# Beta24_mt.net
KiCad netlist of a schematic drawn in EAGLE
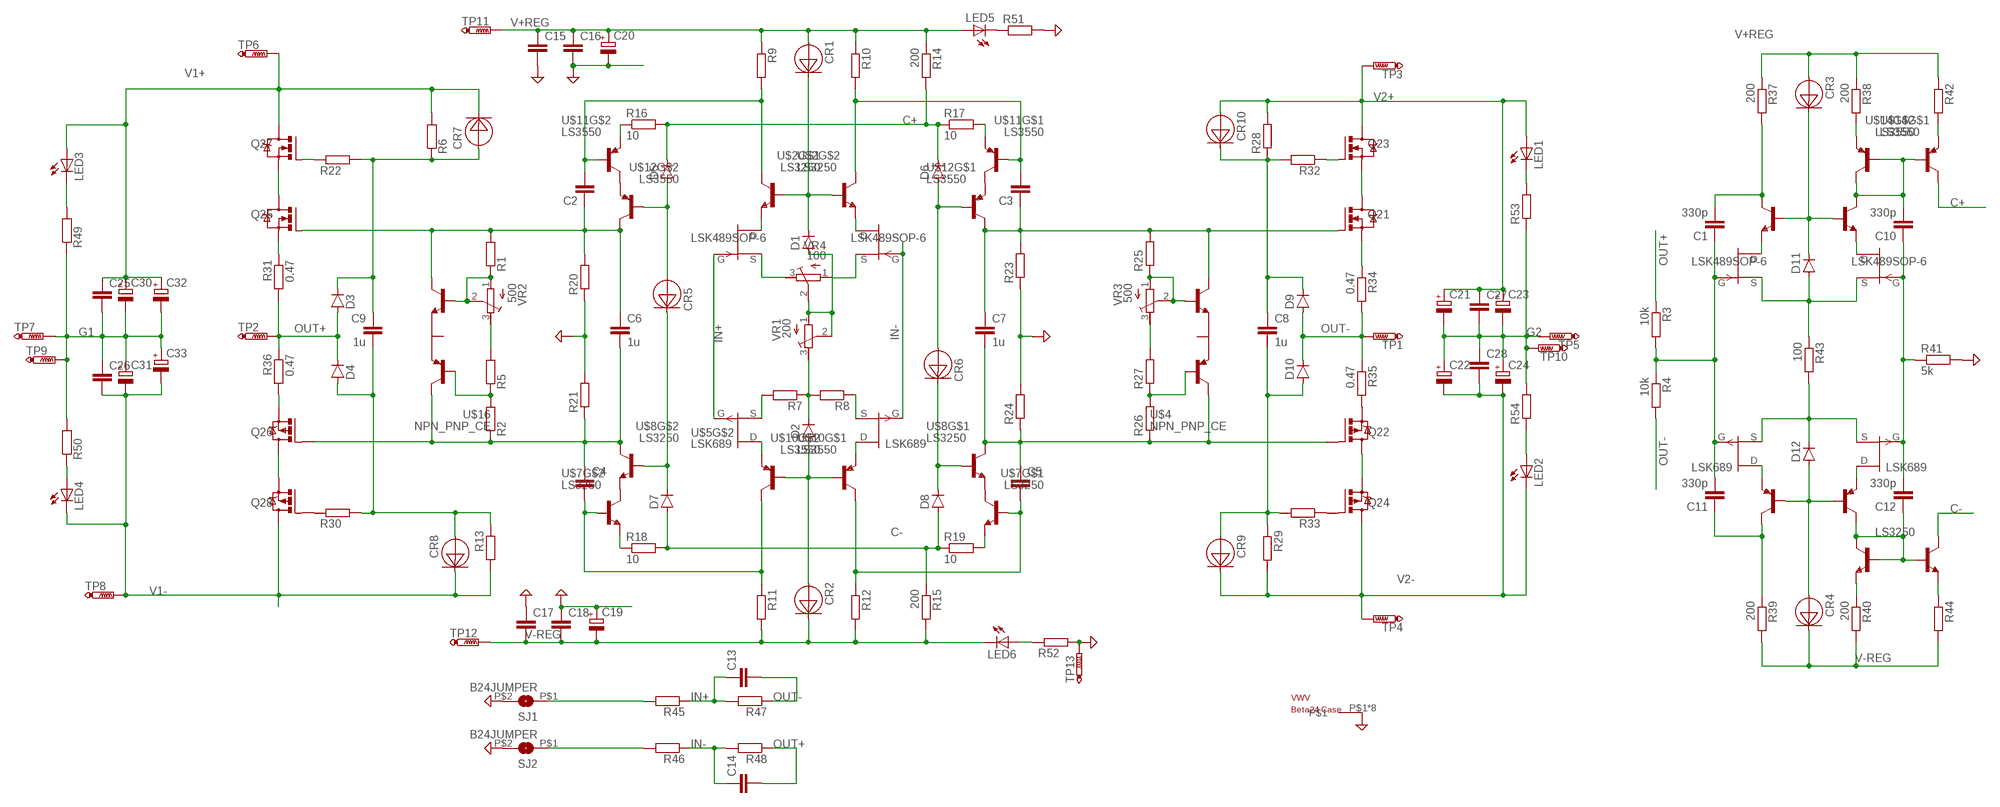
[diagram p0: schematic, sheet 1]

(export (version "E")
  (design (tool "Eeschema 10.0.6"))
  (components
    (comp (ref "C1")
      (value "330p")
      (footprint "eagle-import:C1206")
      (libsource (lib "eagle-import") (part "C-EUC1206"))
    )
    (comp (ref "C2")
      (value "C-EUC1206")
      (footprint "eagle-import:C1206")
      (libsource (lib "eagle-import") (part "C-EUC1206"))
    )
    (comp (ref "C3")
      (value "C-EUC1206")
      (footprint "eagle-import:C1206")
      (libsource (lib "eagle-import") (part "C-EUC1206"))
    )
    (comp (ref "C4")
      (value "C-EUC1206")
      (footprint "eagle-import:C1206")
      (libsource (lib "eagle-import") (part "C-EUC1206"))
    )
    (comp (ref "C5")
      (value "C-EUC1206")
      (footprint "eagle-import:C1206")
      (libsource (lib "eagle-import") (part "C-EUC1206"))
    )
    (comp (ref "C6")
      (value "1u")
      (footprint "eagle-import:C1210")
      (libsource (lib "eagle-import") (part "C-EUC1210"))
    )
    (comp (ref "C7")
      (value "1u")
      (footprint "eagle-import:C1210")
      (libsource (lib "eagle-import") (part "C-EUC1210"))
    )
    (comp (ref "C8")
      (value "1u")
      (footprint "eagle-import:C1206")
      (libsource (lib "eagle-import") (part "C-EUC1206"))
    )
    (comp (ref "C9")
      (value "1u")
      (footprint "eagle-import:C1206")
      (libsource (lib "eagle-import") (part "C-EUC1206"))
    )
    (comp (ref "C10")
      (value "330p")
      (footprint "eagle-import:C1206")
      (libsource (lib "eagle-import") (part "C-EUC1206"))
    )
    (comp (ref "C11")
      (value "330p")
      (footprint "eagle-import:C1206")
      (libsource (lib "eagle-import") (part "C-EUC1206"))
    )
    (comp (ref "C12")
      (value "330p")
      (footprint "eagle-import:C1206")
      (libsource (lib "eagle-import") (part "C-EUC1206"))
    )
    (comp (ref "C13")
      (value "C-EUC1206")
      (footprint "eagle-import:C1206")
      (libsource (lib "eagle-import") (part "C-EUC1206"))
    )
    (comp (ref "C14")
      (value "C-EUC1206")
      (footprint "eagle-import:C1206")
      (libsource (lib "eagle-import") (part "C-EUC1206"))
    )
    (comp (ref "C15")
      (value "C-EUC1206")
      (footprint "eagle-import:C1206")
      (libsource (lib "eagle-import") (part "C-EUC1206"))
    )
    (comp (ref "C16")
      (value "C-EUC1206")
      (footprint "eagle-import:C1206")
      (libsource (lib "eagle-import") (part "C-EUC1206"))
    )
    (comp (ref "C17")
      (value "C-EUC1206")
      (footprint "eagle-import:C1206")
      (libsource (lib "eagle-import") (part "C-EUC1206"))
    )
    (comp (ref "C18")
      (value "C-EUC1206")
      (footprint "eagle-import:C1206")
      (libsource (lib "eagle-import") (part "C-EUC1206"))
    )
    (comp (ref "C19")
      (value "CPOL-EUG")
      (footprint "eagle-import:PANASONIC_G")
      (libsource (lib "eagle-import") (part "CPOL-EUG"))
    )
    (comp (ref "C20")
      (value "CPOL-EUG")
      (footprint "eagle-import:PANASONIC_G")
      (libsource (lib "eagle-import") (part "CPOL-EUG"))
    )
    (comp (ref "C21")
      (value "CPOL-EUG")
      (footprint "eagle-import:PANASONIC_G")
      (libsource (lib "eagle-import") (part "CPOL-EUG"))
    )
    (comp (ref "C22")
      (value "CPOL-EUG")
      (footprint "eagle-import:PANASONIC_G")
      (libsource (lib "eagle-import") (part "CPOL-EUG"))
    )
    (comp (ref "C23")
      (value "CPOL-EUG")
      (footprint "eagle-import:PANASONIC_G")
      (libsource (lib "eagle-import") (part "CPOL-EUG"))
    )
    (comp (ref "C24")
      (value "CPOL-EUG")
      (footprint "eagle-import:PANASONIC_G")
      (libsource (lib "eagle-import") (part "CPOL-EUG"))
    )
    (comp (ref "C25")
      (value "C-EUC1206")
      (footprint "eagle-import:C1206")
      (libsource (lib "eagle-import") (part "C-EUC1206"))
    )
    (comp (ref "C26")
      (value "C-EUC1206")
      (footprint "eagle-import:C1206")
      (libsource (lib "eagle-import") (part "C-EUC1206"))
    )
    (comp (ref "C27")
      (value "C-EUC1206")
      (footprint "eagle-import:C1206")
      (libsource (lib "eagle-import") (part "C-EUC1206"))
    )
    (comp (ref "C28")
      (value "C-EUC1206")
      (footprint "eagle-import:C1206")
      (libsource (lib "eagle-import") (part "C-EUC1206"))
    )
    (comp (ref "C30")
      (value "CPOL-EUG")
      (footprint "eagle-import:PANASONIC_G")
      (libsource (lib "eagle-import") (part "CPOL-EUG"))
    )
    (comp (ref "C31")
      (value "CPOL-EUG")
      (footprint "eagle-import:PANASONIC_G")
      (libsource (lib "eagle-import") (part "CPOL-EUG"))
    )
    (comp (ref "C32")
      (value "CPOL-EUG")
      (footprint "eagle-import:PANASONIC_G")
      (libsource (lib "eagle-import") (part "CPOL-EUG"))
    )
    (comp (ref "C33")
      (value "CPOL-EUG")
      (footprint "eagle-import:PANASONIC_G")
      (libsource (lib "eagle-import") (part "CPOL-EUG"))
    )
    (comp (ref "CR1")
      (value "1N5283")
      (footprint "eagle-import:SMD")
      (libsource (lib "eagle-import") (part "1N5283"))
    )
    (comp (ref "CR2")
      (value "1N5283")
      (footprint "eagle-import:SMD")
      (libsource (lib "eagle-import") (part "1N5283"))
    )
    (comp (ref "CR3")
      (value "1N5283")
      (footprint "eagle-import:SMD")
      (libsource (lib "eagle-import") (part "1N5283"))
    )
    (comp (ref "CR4")
      (value "1N5283")
      (footprint "eagle-import:SMD")
      (libsource (lib "eagle-import") (part "1N5283"))
    )
    (comp (ref "CR5")
      (value "1N5283")
      (footprint "eagle-import:SMD")
      (libsource (lib "eagle-import") (part "1N5283"))
    )
    (comp (ref "CR6")
      (value "1N5283")
      (footprint "eagle-import:SMD")
      (libsource (lib "eagle-import") (part "1N5283"))
    )
    (comp (ref "CR7")
      (value "1N5283")
      (footprint "eagle-import:SMD")
      (libsource (lib "eagle-import") (part "1N5283"))
    )
    (comp (ref "CR8")
      (value "1N5283")
      (footprint "eagle-import:SMD")
      (libsource (lib "eagle-import") (part "1N5283"))
    )
    (comp (ref "CR9")
      (value "1N5283")
      (footprint "eagle-import:SMD")
      (libsource (lib "eagle-import") (part "1N5283"))
    )
    (comp (ref "CR10")
      (value "1N5283")
      (footprint "eagle-import:SMD")
      (libsource (lib "eagle-import") (part "1N5283"))
    )
    (comp (ref "D1")
      (value "DIODE-SOD80C")
      (footprint "eagle-import:SOD80C")
      (libsource (lib "eagle-import") (part "DIODE-SOD80C"))
    )
    (comp (ref "D2")
      (value "DIODE-SOD80C")
      (footprint "eagle-import:SOD80C")
      (libsource (lib "eagle-import") (part "DIODE-SOD80C"))
    )
    (comp (ref "D3")
      (value "DIODE-SOD80C")
      (footprint "eagle-import:SOD80C")
      (libsource (lib "eagle-import") (part "DIODE-SOD80C"))
    )
    (comp (ref "D4")
      (value "DIODE-SOD80C")
      (footprint "eagle-import:SOD80C")
      (libsource (lib "eagle-import") (part "DIODE-SOD80C"))
    )
    (comp (ref "D5")
      (value "DIODE-SOD80C")
      (footprint "eagle-import:SOD80C")
      (libsource (lib "eagle-import") (part "DIODE-SOD80C"))
    )
    (comp (ref "D6")
      (value "DIODE-SOD80C")
      (footprint "eagle-import:SOD80C")
      (libsource (lib "eagle-import") (part "DIODE-SOD80C"))
    )
    (comp (ref "D7")
      (value "DIODE-SOD80C")
      (footprint "eagle-import:SOD80C")
      (libsource (lib "eagle-import") (part "DIODE-SOD80C"))
    )
    (comp (ref "D8")
      (value "DIODE-SOD80C")
      (footprint "eagle-import:SOD80C")
      (libsource (lib "eagle-import") (part "DIODE-SOD80C"))
    )
    (comp (ref "D9")
      (value "DIODE-SOD80C")
      (footprint "eagle-import:SOD80C")
      (libsource (lib "eagle-import") (part "DIODE-SOD80C"))
    )
    (comp (ref "D10")
      (value "DIODE-SOD80C")
      (footprint "eagle-import:SOD80C")
      (libsource (lib "eagle-import") (part "DIODE-SOD80C"))
    )
    (comp (ref "D11")
      (value "DIODE-SOD80C")
      (footprint "eagle-import:SOD80C")
      (libsource (lib "eagle-import") (part "DIODE-SOD80C"))
    )
    (comp (ref "D12")
      (value "DIODE-SOD80C")
      (footprint "eagle-import:SOD80C")
      (libsource (lib "eagle-import") (part "DIODE-SOD80C"))
    )
    (comp (ref "LED1")
      (value "LED_LEDSML1206")
      (footprint "eagle-import:LED_SML1206")
      (libsource (lib "eagle-import") (part "LED_LEDSML1206"))
    )
    (comp (ref "LED2")
      (value "LED_LEDSML1206")
      (footprint "eagle-import:LED_SML1206")
      (libsource (lib "eagle-import") (part "LED_LEDSML1206"))
    )
    (comp (ref "LED3")
      (value "LED_LEDSML1206")
      (footprint "eagle-import:LED_SML1206")
      (libsource (lib "eagle-import") (part "LED_LEDSML1206"))
    )
    (comp (ref "LED4")
      (value "LED_LEDSML1206")
      (footprint "eagle-import:LED_SML1206")
      (libsource (lib "eagle-import") (part "LED_LEDSML1206"))
    )
    (comp (ref "LED5")
      (value "LED_LEDSML1206")
      (footprint "eagle-import:LED_SML1206")
      (libsource (lib "eagle-import") (part "LED_LEDSML1206"))
    )
    (comp (ref "LED6")
      (value "LED_LEDSML1206")
      (footprint "eagle-import:LED_SML1206")
      (libsource (lib "eagle-import") (part "LED_LEDSML1206"))
    )
    (comp (ref "Q21")
      (value "IRFZ24ND2PAK")
      (footprint "eagle-import:TO254P1054X240-3M")
      (libsource (lib "eagle-import") (part "IRFZ24ND2PAK"))
    )
    (comp (ref "Q22")
      (value "IRF9Z34D2PAK")
      (footprint "eagle-import:TO254P1054X240-3M")
      (libsource (lib "eagle-import") (part "IRF9Z34D2PAK"))
    )
    (comp (ref "Q23")
      (value "IRFZ24ND2PAK")
      (footprint "eagle-import:TO254P1054X240-3M")
      (libsource (lib "eagle-import") (part "IRFZ24ND2PAK"))
    )
    (comp (ref "Q24")
      (value "IRF9Z34D2PAK")
      (footprint "eagle-import:TO254P1054X240-3M")
      (libsource (lib "eagle-import") (part "IRF9Z34D2PAK"))
    )
    (comp (ref "Q25")
      (value "IRFZ24ND2PAK")
      (footprint "eagle-import:TO254P1054X240-3M")
      (libsource (lib "eagle-import") (part "IRFZ24ND2PAK"))
    )
    (comp (ref "Q26")
      (value "IRF9Z34D2PAK")
      (footprint "eagle-import:TO254P1054X240-3M")
      (libsource (lib "eagle-import") (part "IRF9Z34D2PAK"))
    )
    (comp (ref "Q27")
      (value "IRFZ24ND2PAK")
      (footprint "eagle-import:TO254P1054X240-3M")
      (libsource (lib "eagle-import") (part "IRFZ24ND2PAK"))
    )
    (comp (ref "Q28")
      (value "IRF9Z34D2PAK")
      (footprint "eagle-import:TO254P1054X240-3M")
      (libsource (lib "eagle-import") (part "IRF9Z34D2PAK"))
    )
    (comp (ref "R1")
      (value "R-EU_MELF0204W")
      (footprint "eagle-import:MINI_MELF-0204W")
      (libsource (lib "eagle-import") (part "R-EU_MELF0204W"))
    )
    (comp (ref "R2")
      (value "R-EU_MELF0204W")
      (footprint "eagle-import:MINI_MELF-0204W")
      (libsource (lib "eagle-import") (part "R-EU_MELF0204W"))
    )
    (comp (ref "R3")
      (value "10k")
      (footprint "eagle-import:MINI_MELF-0204W")
      (libsource (lib "eagle-import") (part "R-EU_MELF0204W"))
    )
    (comp (ref "R4")
      (value "10k")
      (footprint "eagle-import:MINI_MELF-0204W")
      (libsource (lib "eagle-import") (part "R-EU_MELF0204W"))
    )
    (comp (ref "R5")
      (value "R-EU_MELF0204W")
      (footprint "eagle-import:MINI_MELF-0204W")
      (libsource (lib "eagle-import") (part "R-EU_MELF0204W"))
    )
    (comp (ref "R6")
      (value "R-EU_MELF0204W")
      (footprint "eagle-import:MINI_MELF-0204W")
      (libsource (lib "eagle-import") (part "R-EU_MELF0204W"))
    )
    (comp (ref "R7")
      (value "R-EU_MELF0204W")
      (footprint "eagle-import:MINI_MELF-0204W")
      (libsource (lib "eagle-import") (part "R-EU_MELF0204W"))
    )
    (comp (ref "R8")
      (value "R-EU_MELF0204W")
      (footprint "eagle-import:MINI_MELF-0204W")
      (libsource (lib "eagle-import") (part "R-EU_MELF0204W"))
    )
    (comp (ref "R9")
      (value "R-EU_MELF0204W")
      (footprint "eagle-import:MINI_MELF-0204W")
      (libsource (lib "eagle-import") (part "R-EU_MELF0204W"))
    )
    (comp (ref "R10")
      (value "R-EU_MELF0204W")
      (footprint "eagle-import:MINI_MELF-0204W")
      (libsource (lib "eagle-import") (part "R-EU_MELF0204W"))
    )
    (comp (ref "R11")
      (value "R-EU_MELF0204W")
      (footprint "eagle-import:MINI_MELF-0204W")
      (libsource (lib "eagle-import") (part "R-EU_MELF0204W"))
    )
    (comp (ref "R12")
      (value "R-EU_MELF0204W")
      (footprint "eagle-import:MINI_MELF-0204W")
      (libsource (lib "eagle-import") (part "R-EU_MELF0204W"))
    )
    (comp (ref "R13")
      (value "R-EU_MELF0204W")
      (footprint "eagle-import:MINI_MELF-0204W")
      (libsource (lib "eagle-import") (part "R-EU_MELF0204W"))
    )
    (comp (ref "R14")
      (value "200")
      (footprint "eagle-import:MINI_MELF-0204W")
      (libsource (lib "eagle-import") (part "R-EU_MELF0204W"))
    )
    (comp (ref "R15")
      (value "200")
      (footprint "eagle-import:MINI_MELF-0204W")
      (libsource (lib "eagle-import") (part "R-EU_MELF0204W"))
    )
    (comp (ref "R16")
      (value "10")
      (footprint "eagle-import:MINI_MELF-0204W")
      (libsource (lib "eagle-import") (part "R-EU_MELF0204W"))
    )
    (comp (ref "R17")
      (value "10")
      (footprint "eagle-import:MINI_MELF-0204W")
      (libsource (lib "eagle-import") (part "R-EU_MELF0204W"))
    )
    (comp (ref "R18")
      (value "10")
      (footprint "eagle-import:MINI_MELF-0204W")
      (libsource (lib "eagle-import") (part "R-EU_MELF0204W"))
    )
    (comp (ref "R19")
      (value "10")
      (footprint "eagle-import:MINI_MELF-0204W")
      (libsource (lib "eagle-import") (part "R-EU_MELF0204W"))
    )
    (comp (ref "R20")
      (value "R-EU_MELF0204W")
      (footprint "eagle-import:MINI_MELF-0204W")
      (libsource (lib "eagle-import") (part "R-EU_MELF0204W"))
    )
    (comp (ref "R21")
      (value "R-EU_MELF0204W")
      (footprint "eagle-import:MINI_MELF-0204W")
      (libsource (lib "eagle-import") (part "R-EU_MELF0204W"))
    )
    (comp (ref "R22")
      (value "R-EU_MELF0204W")
      (footprint "eagle-import:MINI_MELF-0204W")
      (libsource (lib "eagle-import") (part "R-EU_MELF0204W"))
    )
    (comp (ref "R23")
      (value "R-EU_MELF0204W")
      (footprint "eagle-import:MINI_MELF-0204W")
      (libsource (lib "eagle-import") (part "R-EU_MELF0204W"))
    )
    (comp (ref "R24")
      (value "R-EU_MELF0204W")
      (footprint "eagle-import:MINI_MELF-0204W")
      (libsource (lib "eagle-import") (part "R-EU_MELF0204W"))
    )
    (comp (ref "R25")
      (value "R-EU_MELF0204W")
      (footprint "eagle-import:MINI_MELF-0204W")
      (libsource (lib "eagle-import") (part "R-EU_MELF0204W"))
    )
    (comp (ref "R26")
      (value "R-EU_MELF0204W")
      (footprint "eagle-import:MINI_MELF-0204W")
      (libsource (lib "eagle-import") (part "R-EU_MELF0204W"))
    )
    (comp (ref "R27")
      (value "R-EU_MELF0204W")
      (footprint "eagle-import:MINI_MELF-0204W")
      (libsource (lib "eagle-import") (part "R-EU_MELF0204W"))
    )
    (comp (ref "R28")
      (value "R-EU_MELF0204W")
      (footprint "eagle-import:MINI_MELF-0204W")
      (libsource (lib "eagle-import") (part "R-EU_MELF0204W"))
    )
    (comp (ref "R29")
      (value "R-EU_MELF0204W")
      (footprint "eagle-import:MINI_MELF-0204W")
      (libsource (lib "eagle-import") (part "R-EU_MELF0204W"))
    )
    (comp (ref "R30")
      (value "R-EU_MELF0204W")
      (footprint "eagle-import:MINI_MELF-0204W")
      (libsource (lib "eagle-import") (part "R-EU_MELF0204W"))
    )
    (comp (ref "R31")
      (value "0.47")
      (footprint "eagle-import:R2512")
      (libsource (lib "eagle-import") (part "R-EU_R2512"))
    )
    (comp (ref "R32")
      (value "R-EU_MELF0204W")
      (footprint "eagle-import:MINI_MELF-0204W")
      (libsource (lib "eagle-import") (part "R-EU_MELF0204W"))
    )
    (comp (ref "R33")
      (value "R-EU_MELF0204W")
      (footprint "eagle-import:MINI_MELF-0204W")
      (libsource (lib "eagle-import") (part "R-EU_MELF0204W"))
    )
    (comp (ref "R34")
      (value "0.47")
      (footprint "eagle-import:R2512")
      (libsource (lib "eagle-import") (part "R-EU_R2512"))
    )
    (comp (ref "R35")
      (value "0.47")
      (footprint "eagle-import:R2512")
      (libsource (lib "eagle-import") (part "R-EU_R2512"))
    )
    (comp (ref "R36")
      (value "0.47")
      (footprint "eagle-import:R2512")
      (libsource (lib "eagle-import") (part "R-EU_R2512"))
    )
    (comp (ref "R37")
      (value "200")
      (footprint "eagle-import:MINI_MELF-0204W")
      (libsource (lib "eagle-import") (part "R-EU_MELF0204W"))
    )
    (comp (ref "R38")
      (value "200")
      (footprint "eagle-import:MINI_MELF-0204W")
      (libsource (lib "eagle-import") (part "R-EU_MELF0204W"))
    )
    (comp (ref "R39")
      (value "200")
      (footprint "eagle-import:MINI_MELF-0204W")
      (libsource (lib "eagle-import") (part "R-EU_MELF0204W"))
    )
    (comp (ref "R40")
      (value "200")
      (footprint "eagle-import:MINI_MELF-0204W")
      (libsource (lib "eagle-import") (part "R-EU_MELF0204W"))
    )
    (comp (ref "R41")
      (value "5k")
      (footprint "eagle-import:MINI_MELF-0204W")
      (libsource (lib "eagle-import") (part "R-EU_MELF0204W"))
    )
    (comp (ref "R42")
      (value "R-EU_MELF0204W")
      (footprint "eagle-import:MINI_MELF-0204W")
      (libsource (lib "eagle-import") (part "R-EU_MELF0204W"))
    )
    (comp (ref "R43")
      (value "100")
      (footprint "eagle-import:MINI_MELF-0204W")
      (libsource (lib "eagle-import") (part "R-EU_MELF0204W"))
    )
    (comp (ref "R44")
      (value "R-EU_MELF0204W")
      (footprint "eagle-import:MINI_MELF-0204W")
      (libsource (lib "eagle-import") (part "R-EU_MELF0204W"))
    )
    (comp (ref "R45")
      (value "R-EU_MELF0204W")
      (footprint "eagle-import:MINI_MELF-0204W")
      (libsource (lib "eagle-import") (part "R-EU_MELF0204W"))
    )
    (comp (ref "R46")
      (value "R-EU_MELF0204W")
      (footprint "eagle-import:MINI_MELF-0204W")
      (libsource (lib "eagle-import") (part "R-EU_MELF0204W"))
    )
    (comp (ref "R47")
      (value "R-EU_MELF0204W")
      (footprint "eagle-import:MINI_MELF-0204W")
      (libsource (lib "eagle-import") (part "R-EU_MELF0204W"))
    )
    (comp (ref "R48")
      (value "R-EU_MELF0204W")
      (footprint "eagle-import:MINI_MELF-0204W")
      (libsource (lib "eagle-import") (part "R-EU_MELF0204W"))
    )
    (comp (ref "R49")
      (value "R-EU_MELF0204W")
      (footprint "eagle-import:MINI_MELF-0204W")
      (libsource (lib "eagle-import") (part "R-EU_MELF0204W"))
    )
    (comp (ref "R50")
      (value "R-EU_MELF0204W")
      (footprint "eagle-import:MINI_MELF-0204W")
      (libsource (lib "eagle-import") (part "R-EU_MELF0204W"))
    )
    (comp (ref "R51")
      (value "200")
      (footprint "eagle-import:MINI_MELF-0204W")
      (libsource (lib "eagle-import") (part "R-EU_MELF0204W"))
    )
    (comp (ref "R52")
      (value "R-EU_MELF0204W")
      (footprint "eagle-import:MINI_MELF-0204W")
      (libsource (lib "eagle-import") (part "R-EU_MELF0204W"))
    )
    (comp (ref "R53")
      (value "R-EU_MELF0204W")
      (footprint "eagle-import:MINI_MELF-0204W")
      (libsource (lib "eagle-import") (part "R-EU_MELF0204W"))
    )
    (comp (ref "R54")
      (value "R-EU_MELF0204W")
      (footprint "eagle-import:MINI_MELF-0204W")
      (libsource (lib "eagle-import") (part "R-EU_MELF0204W"))
    )
    (comp (ref "SJ1")
      (value "B24JUMPER")
      (footprint "eagle-import:B24J")
      (libsource (lib "eagle-import") (part "B24JUMPER"))
    )
    (comp (ref "SJ2")
      (value "B24JUMPER")
      (footprint "eagle-import:B24J")
      (libsource (lib "eagle-import") (part "B24JUMPER"))
    )
    (comp (ref "TP1")
      (value "PTR1PAD1-20")
      (footprint "eagle-import:P1-20")
      (libsource (lib "eagle-import") (part "PTR1PAD1-20"))
    )
    (comp (ref "TP2")
      (value "PTR1PAD1-20")
      (footprint "eagle-import:P1-20")
      (libsource (lib "eagle-import") (part "PTR1PAD1-20"))
    )
    (comp (ref "TP3")
      (value "PTR1PAD1-20")
      (footprint "eagle-import:P1-20")
      (libsource (lib "eagle-import") (part "PTR1PAD1-20"))
    )
    (comp (ref "TP4")
      (value "PTR1PAD1-20")
      (footprint "eagle-import:P1-20")
      (libsource (lib "eagle-import") (part "PTR1PAD1-20"))
    )
    (comp (ref "TP5")
      (value "PTR1PAD1-20")
      (footprint "eagle-import:P1-20")
      (libsource (lib "eagle-import") (part "PTR1PAD1-20"))
    )
    (comp (ref "TP6")
      (value "PTR1PAD1-20")
      (footprint "eagle-import:P1-20")
      (libsource (lib "eagle-import") (part "PTR1PAD1-20"))
    )
    (comp (ref "TP7")
      (value "PTR1PAD1-20")
      (footprint "eagle-import:P1-20")
      (libsource (lib "eagle-import") (part "PTR1PAD1-20"))
    )
    (comp (ref "TP8")
      (value "PTR1PAD1-20")
      (footprint "eagle-import:P1-20")
      (libsource (lib "eagle-import") (part "PTR1PAD1-20"))
    )
    (comp (ref "TP9")
      (value "PTR1PAD1-20")
      (footprint "eagle-import:P1-20")
      (libsource (lib "eagle-import") (part "PTR1PAD1-20"))
    )
    (comp (ref "TP10")
      (value "PTR1PAD1-20")
      (footprint "eagle-import:P1-20")
      (libsource (lib "eagle-import") (part "PTR1PAD1-20"))
    )
    (comp (ref "TP11")
      (value "PTR1PAD1-20")
      (footprint "eagle-import:P1-20")
      (libsource (lib "eagle-import") (part "PTR1PAD1-20"))
    )
    (comp (ref "TP12")
      (value "PTR1PAD1-20")
      (footprint "eagle-import:P1-20")
      (libsource (lib "eagle-import") (part "PTR1PAD1-20"))
    )
    (comp (ref "TP13")
      (value "PTR1PAD1-20")
      (footprint "eagle-import:P1-20")
      (libsource (lib "eagle-import") (part "PTR1PAD1-20"))
    )
    (comp (ref "U$1")
      (value "LSK489SOP-6")
      (footprint "eagle-import:SOT-23-6")
      (libsource (lib "eagle-import") (part "LSK489SOP-6"))
    )
    (comp (ref "U$2")
      (value "LS3250")
      (footprint "eagle-import:SOT-23-6")
      (libsource (lib "eagle-import") (part "LS3250"))
    )
    (comp (ref "U$3")
      (value "LSK489SOP-6")
      (footprint "eagle-import:SOT-23-6")
      (libsource (lib "eagle-import") (part "LSK489SOP-6"))
    )
    (comp (ref "U$4")
      (value "NPN_PNP_CE")
      (footprint "eagle-import:SOT25")
      (libsource (lib "eagle-import") (part "NPN_PNP_CE"))
    )
    (comp (ref "U$5")
      (value "LSK689")
      (footprint "eagle-import:SOT-23-6")
      (libsource (lib "eagle-import") (part "LSK689"))
    )
    (comp (ref "U$6")
      (value "LS3250")
      (footprint "eagle-import:SOT-23-6")
      (libsource (lib "eagle-import") (part "LS3250"))
    )
    (comp (ref "U$7")
      (value "LS3250")
      (footprint "eagle-import:SOT-23-6")
      (libsource (lib "eagle-import") (part "LS3250"))
    )
    (comp (ref "U$8")
      (value "LS3250")
      (footprint "eagle-import:SOT-23-6")
      (libsource (lib "eagle-import") (part "LS3250"))
    )
    (comp (ref "U$9")
      (value "LS3550")
      (footprint "eagle-import:SOT-23-6")
      (libsource (lib "eagle-import") (part "LS3550"))
    )
    (comp (ref "U$10")
      (value "LS3550")
      (footprint "eagle-import:SOT-23-6")
      (libsource (lib "eagle-import") (part "LS3550"))
    )
    (comp (ref "U$11")
      (value "LS3550")
      (footprint "eagle-import:SOT-23-6")
      (libsource (lib "eagle-import") (part "LS3550"))
    )
    (comp (ref "U$12")
      (value "LS3550")
      (footprint "eagle-import:SOT-23-6")
      (libsource (lib "eagle-import") (part "LS3550"))
    )
    (comp (ref "U$13")
      (value "LS3250")
      (footprint "eagle-import:SOT-23-6")
      (libsource (lib "eagle-import") (part "LS3250"))
    )
    (comp (ref "U$14")
      (value "LS3550")
      (footprint "eagle-import:SOT-23-6")
      (libsource (lib "eagle-import") (part "LS3550"))
    )
    (comp (ref "U$15")
      (value "LSK689")
      (footprint "eagle-import:SOT-23-6")
      (libsource (lib "eagle-import") (part "LSK689"))
    )
    (comp (ref "U$16")
      (value "NPN_PNP_CE")
      (footprint "eagle-import:SOT25")
      (libsource (lib "eagle-import") (part "NPN_PNP_CE"))
    )
    (comp (ref "U$17")
      (value "VWV")
      (footprint "eagle-import:VWV")
      (libsource (lib "eagle-import") (part "VWV"))
    )
    (comp (ref "U$18")
      (value "B24C")
      (footprint "eagle-import:B24C")
      (libsource (lib "eagle-import") (part "B24C"))
    )
    (comp (ref "VR1")
      (value "200")
      (footprint "eagle-import:RTRIM3296W")
      (libsource (lib "eagle-import") (part "R-TRIMM3296W"))
    )
    (comp (ref "VR2")
      (value "500")
      (footprint "eagle-import:RTRIM3296W")
      (libsource (lib "eagle-import") (part "R-TRIMM3296W"))
    )
    (comp (ref "VR3")
      (value "500")
      (footprint "eagle-import:RTRIM3296W")
      (libsource (lib "eagle-import") (part "R-TRIMM3296W"))
    )
    (comp (ref "VR4")
      (value "100")
      (footprint "eagle-import:RTRIM3296W")
      (libsource (lib "eagle-import") (part "R-TRIMM3296W"))
    )
  )
  (nets
    (net (code "1") (name "/C+") (class "Default")
      (node (ref "D5") (pin "C") (pinfunction "C_C") (pintype "passive"))
      (node (ref "D6") (pin "C") (pinfunction "C_C") (pintype "passive"))
      (node (ref "R14") (pin "2") (pinfunction "2_2") (pintype "passive"))
      (node (ref "R16") (pin "2") (pinfunction "2_2") (pintype "passive"))
      (node (ref "R17") (pin "1") (pinfunction "1_1") (pintype "passive"))
      (node (ref "U$14") (pin "6") (pinfunction "C_6") (pintype "passive"))
    )
    (net (code "2") (name "/C-") (class "Default")
      (node (ref "D7") (pin "A") (pinfunction "A_A") (pintype "passive"))
      (node (ref "D8") (pin "A") (pinfunction "A_A") (pintype "passive"))
      (node (ref "R15") (pin "1") (pinfunction "1_1") (pintype "passive"))
      (node (ref "R18") (pin "2") (pinfunction "2_2") (pintype "passive"))
      (node (ref "R19") (pin "1") (pinfunction "1_1") (pintype "passive"))
      (node (ref "U$13") (pin "6") (pinfunction "C_6") (pintype "passive"))
    )
    (net (code "3") (name "/G1") (class "Default")
      (node (ref "C25") (pin "2") (pinfunction "2_2") (pintype "passive"))
      (node (ref "C26") (pin "1") (pinfunction "1_1") (pintype "passive"))
      (node (ref "C30") (pin "-") (pinfunction "-_-") (pintype "passive"))
      (node (ref "C31") (pin "+") (pinfunction "+_+") (pintype "passive"))
      (node (ref "C32") (pin "-") (pinfunction "-_-") (pintype "passive"))
      (node (ref "C33") (pin "+") (pinfunction "+_+") (pintype "passive"))
      (node (ref "R49") (pin "1") (pinfunction "1_1") (pintype "passive"))
      (node (ref "R50") (pin "2") (pinfunction "2_2") (pintype "passive"))
      (node (ref "TP7") (pin "TP") (pinfunction "TP_TP") (pintype "input"))
      (node (ref "TP9") (pin "TP") (pinfunction "TP_TP") (pintype "input"))
    )
    (net (code "4") (name "/G2") (class "Default")
      (node (ref "C21") (pin "-") (pinfunction "-_-") (pintype "passive"))
      (node (ref "C22") (pin "+") (pinfunction "+_+") (pintype "passive"))
      (node (ref "C23") (pin "-") (pinfunction "-_-") (pintype "passive"))
      (node (ref "C24") (pin "+") (pinfunction "+_+") (pintype "passive"))
      (node (ref "C27") (pin "2") (pinfunction "2_2") (pintype "passive"))
      (node (ref "C28") (pin "1") (pinfunction "1_1") (pintype "passive"))
      (node (ref "R53") (pin "1") (pinfunction "1_1") (pintype "passive"))
      (node (ref "R54") (pin "2") (pinfunction "2_2") (pintype "passive"))
      (node (ref "TP10") (pin "TP") (pinfunction "TP_TP") (pintype "input"))
      (node (ref "TP5") (pin "TP") (pinfunction "TP_TP") (pintype "input"))
    )
    (net (code "5") (name "/IN+") (class "Default")
      (node (ref "C13") (pin "1") (pinfunction "1_1") (pintype "passive"))
      (node (ref "R45") (pin "1") (pinfunction "1_1") (pintype "passive"))
      (node (ref "R47") (pin "2") (pinfunction "2_2") (pintype "passive"))
      (node (ref "U$1") (pin "1") (pinfunction "G_1") (pintype "passive"))
      (node (ref "U$5") (pin "4") (pinfunction "G_4") (pintype "passive"))
    )
    (net (code "6") (name "/IN-") (class "Default")
      (node (ref "C14") (pin "1") (pinfunction "1_1") (pintype "passive"))
      (node (ref "R46") (pin "1") (pinfunction "1_1") (pintype "passive"))
      (node (ref "R48") (pin "2") (pinfunction "2_2") (pintype "passive"))
      (node (ref "U$1") (pin "4") (pinfunction "G_4") (pintype "passive"))
      (node (ref "U$5") (pin "1") (pinfunction "G_1") (pintype "passive"))
    )
    (net (code "7") (name "/OUT+") (class "Default")
      (node (ref "C14") (pin "2") (pinfunction "2_2") (pintype "passive"))
      (node (ref "D3") (pin "A") (pinfunction "A_A") (pintype "passive"))
      (node (ref "D4") (pin "C") (pinfunction "C_C") (pintype "passive"))
      (node (ref "R3") (pin "1") (pinfunction "1_1") (pintype "passive"))
      (node (ref "R31") (pin "2") (pinfunction "2_2") (pintype "passive"))
      (node (ref "R36") (pin "1") (pinfunction "1_1") (pintype "passive"))
      (node (ref "R48") (pin "1") (pinfunction "1_1") (pintype "passive"))
      (node (ref "TP2") (pin "TP") (pinfunction "TP_TP") (pintype "input"))
    )
    (net (code "8") (name "/OUT-") (class "Default")
      (node (ref "C13") (pin "2") (pinfunction "2_2") (pintype "passive"))
      (node (ref "D10") (pin "C") (pinfunction "C_C") (pintype "passive"))
      (node (ref "D9") (pin "A") (pinfunction "A_A") (pintype "passive"))
      (node (ref "R34") (pin "2") (pinfunction "2_2") (pintype "passive"))
      (node (ref "R35") (pin "1") (pinfunction "1_1") (pintype "passive"))
      (node (ref "R4") (pin "2") (pinfunction "2_2") (pintype "passive"))
      (node (ref "R47") (pin "1") (pinfunction "1_1") (pintype "passive"))
      (node (ref "TP1") (pin "TP") (pinfunction "TP_TP") (pintype "input"))
    )
    (net (code "9") (name "/V+REG") (class "Default")
      (node (ref "C15") (pin "1") (pinfunction "1_1") (pintype "passive"))
      (node (ref "C16") (pin "1") (pinfunction "1_1") (pintype "passive"))
      (node (ref "C20") (pin "+") (pinfunction "+_+") (pintype "passive"))
      (node (ref "CR1") (pin "ANODE") (pinfunction "ANODE_ANODE") (pintype "passive"))
      (node (ref "CR3") (pin "ANODE") (pinfunction "ANODE_ANODE") (pintype "passive"))
      (node (ref "LED5") (pin "A") (pinfunction "A_A") (pintype "passive"))
      (node (ref "R10") (pin "1") (pinfunction "1_1") (pintype "passive"))
      (node (ref "R14") (pin "1") (pinfunction "1_1") (pintype "passive"))
      (node (ref "R37") (pin "1") (pinfunction "1_1") (pintype "passive"))
      (node (ref "R38") (pin "1") (pinfunction "1_1") (pintype "passive"))
      (node (ref "R42") (pin "1") (pinfunction "1_1") (pintype "passive"))
      (node (ref "R9") (pin "1") (pinfunction "1_1") (pintype "passive"))
      (node (ref "TP11") (pin "TP") (pinfunction "TP_TP") (pintype "input"))
    )
    (net (code "10") (name "/V-REG") (class "Default")
      (node (ref "C17") (pin "2") (pinfunction "2_2") (pintype "passive"))
      (node (ref "C18") (pin "2") (pinfunction "2_2") (pintype "passive"))
      (node (ref "C19") (pin "-") (pinfunction "-_-") (pintype "passive"))
      (node (ref "CR2") (pin "CATHODE") (pinfunction "CATHODE_CATHODE") (pintype "passive"))
      (node (ref "CR4") (pin "CATHODE") (pinfunction "CATHODE_CATHODE") (pintype "passive"))
      (node (ref "LED6") (pin "C") (pinfunction "C_C") (pintype "passive"))
      (node (ref "R11") (pin "2") (pinfunction "2_2") (pintype "passive"))
      (node (ref "R12") (pin "2") (pinfunction "2_2") (pintype "passive"))
      (node (ref "R15") (pin "2") (pinfunction "2_2") (pintype "passive"))
      (node (ref "R39") (pin "2") (pinfunction "2_2") (pintype "passive"))
      (node (ref "R40") (pin "2") (pinfunction "2_2") (pintype "passive"))
      (node (ref "R44") (pin "2") (pinfunction "2_2") (pintype "passive"))
      (node (ref "TP12") (pin "TP") (pinfunction "TP_TP") (pintype "input"))
    )
    (net (code "11") (name "/V1+") (class "Default")
      (node (ref "C25") (pin "1") (pinfunction "1_1") (pintype "passive"))
      (node (ref "C30") (pin "+") (pinfunction "+_+") (pintype "passive"))
      (node (ref "C32") (pin "+") (pinfunction "+_+") (pintype "passive"))
      (node (ref "CR7") (pin "CATHODE") (pinfunction "CATHODE_CATHODE") (pintype "passive"))
      (node (ref "LED3") (pin "A") (pinfunction "A_A") (pintype "passive"))
      (node (ref "Q27") (pin "2") (pinfunction "D_2") (pintype "passive"))
      (node (ref "Q27") (pin "4") (pinfunction "D_4") (pintype "passive"))
      (node (ref "Q27") (pin "P$1") (pinfunction "D_P$1") (pintype "passive"))
      (node (ref "Q27") (pin "P$10") (pinfunction "D_P$10") (pintype "passive"))
      (node (ref "Q27") (pin "P$11") (pinfunction "D_P$11") (pintype "passive"))
      (node (ref "Q27") (pin "P$12") (pinfunction "D_P$12") (pintype "passive"))
      (node (ref "Q27") (pin "P$13") (pinfunction "D_P$13") (pintype "passive"))
      (node (ref "Q27") (pin "P$14") (pinfunction "D_P$14") (pintype "passive"))
      (node (ref "Q27") (pin "P$15") (pinfunction "D_P$15") (pintype "passive"))
      (node (ref "Q27") (pin "P$16") (pinfunction "D_P$16") (pintype "passive"))
      (node (ref "Q27") (pin "P$17") (pinfunction "D_P$17") (pintype "passive"))
      (node (ref "Q27") (pin "P$18") (pinfunction "D_P$18") (pintype "passive"))
      (node (ref "Q27") (pin "P$19") (pinfunction "D_P$19") (pintype "passive"))
      (node (ref "Q27") (pin "P$2") (pinfunction "D_P$2") (pintype "passive"))
      (node (ref "Q27") (pin "P$20") (pinfunction "D_P$20") (pintype "passive"))
      (node (ref "Q27") (pin "P$21") (pinfunction "D_P$21") (pintype "passive"))
      (node (ref "Q27") (pin "P$22") (pinfunction "D_P$22") (pintype "passive"))
      (node (ref "Q27") (pin "P$23") (pinfunction "D_P$23") (pintype "passive"))
      (node (ref "Q27") (pin "P$24") (pinfunction "D_P$24") (pintype "passive"))
      (node (ref "Q27") (pin "P$25") (pinfunction "D_P$25") (pintype "passive"))
      (node (ref "Q27") (pin "P$26") (pinfunction "D_P$26") (pintype "passive"))
      (node (ref "Q27") (pin "P$27") (pinfunction "D_P$27") (pintype "passive"))
      (node (ref "Q27") (pin "P$28") (pinfunction "D_P$28") (pintype "passive"))
      (node (ref "Q27") (pin "P$29") (pinfunction "D_P$29") (pintype "passive"))
      (node (ref "Q27") (pin "P$3") (pinfunction "D_P$3") (pintype "passive"))
      (node (ref "Q27") (pin "P$30") (pinfunction "D_P$30") (pintype "passive"))
      (node (ref "Q27") (pin "P$31") (pinfunction "D_P$31") (pintype "passive"))
      (node (ref "Q27") (pin "P$32") (pinfunction "D_P$32") (pintype "passive"))
      (node (ref "Q27") (pin "P$33") (pinfunction "D_P$33") (pintype "passive"))
      (node (ref "Q27") (pin "P$34") (pinfunction "D_P$34") (pintype "passive"))
      (node (ref "Q27") (pin "P$35") (pinfunction "D_P$35") (pintype "passive"))
      (node (ref "Q27") (pin "P$36") (pinfunction "D_P$36") (pintype "passive"))
      (node (ref "Q27") (pin "P$37") (pinfunction "D_P$37") (pintype "passive"))
      (node (ref "Q27") (pin "P$38") (pinfunction "D_P$38") (pintype "passive"))
      (node (ref "Q27") (pin "P$39") (pinfunction "D_P$39") (pintype "passive"))
      (node (ref "Q27") (pin "P$4") (pinfunction "D_P$4") (pintype "passive"))
      (node (ref "Q27") (pin "P$40") (pinfunction "D_P$40") (pintype "passive"))
      (node (ref "Q27") (pin "P$41") (pinfunction "D_P$41") (pintype "passive"))
      (node (ref "Q27") (pin "P$42") (pinfunction "D_P$42") (pintype "passive"))
      (node (ref "Q27") (pin "P$43") (pinfunction "D_P$43") (pintype "passive"))
      (node (ref "Q27") (pin "P$44") (pinfunction "D_P$44") (pintype "passive"))
      (node (ref "Q27") (pin "P$45") (pinfunction "D_P$45") (pintype "passive"))
      (node (ref "Q27") (pin "P$46") (pinfunction "D_P$46") (pintype "passive"))
      (node (ref "Q27") (pin "P$47") (pinfunction "D_P$47") (pintype "passive"))
      (node (ref "Q27") (pin "P$48") (pinfunction "D_P$48") (pintype "passive"))
      (node (ref "Q27") (pin "P$49") (pinfunction "D_P$49") (pintype "passive"))
      (node (ref "Q27") (pin "P$5") (pinfunction "D_P$5") (pintype "passive"))
      (node (ref "Q27") (pin "P$50") (pinfunction "D_P$50") (pintype "passive"))
      (node (ref "Q27") (pin "P$51") (pinfunction "D_P$51") (pintype "passive"))
      (node (ref "Q27") (pin "P$52") (pinfunction "D_P$52") (pintype "passive"))
      (node (ref "Q27") (pin "P$53") (pinfunction "D_P$53") (pintype "passive"))
      (node (ref "Q27") (pin "P$54") (pinfunction "D_P$54") (pintype "passive"))
      (node (ref "Q27") (pin "P$55") (pinfunction "D_P$55") (pintype "passive"))
      (node (ref "Q27") (pin "P$56") (pinfunction "D_P$56") (pintype "passive"))
      (node (ref "Q27") (pin "P$57") (pinfunction "D_P$57") (pintype "passive"))
      (node (ref "Q27") (pin "P$58") (pinfunction "D_P$58") (pintype "passive"))
      (node (ref "Q27") (pin "P$59") (pinfunction "D_P$59") (pintype "passive"))
      (node (ref "Q27") (pin "P$6") (pinfunction "D_P$6") (pintype "passive"))
      (node (ref "Q27") (pin "P$60") (pinfunction "D_P$60") (pintype "passive"))
      (node (ref "Q27") (pin "P$61") (pinfunction "D_P$61") (pintype "passive"))
      (node (ref "Q27") (pin "P$62") (pinfunction "D_P$62") (pintype "passive"))
      (node (ref "Q27") (pin "P$63") (pinfunction "D_P$63") (pintype "passive"))
      (node (ref "Q27") (pin "P$7") (pinfunction "D_P$7") (pintype "passive"))
      (node (ref "Q27") (pin "P$8") (pinfunction "D_P$8") (pintype "passive"))
      (node (ref "Q27") (pin "P$9") (pinfunction "D_P$9") (pintype "passive"))
      (node (ref "R6") (pin "2") (pinfunction "2_2") (pintype "passive"))
      (node (ref "TP6") (pin "TP") (pinfunction "TP_TP") (pintype "input"))
    )
    (net (code "12") (name "/V1-") (class "Default")
      (node (ref "C26") (pin "2") (pinfunction "2_2") (pintype "passive"))
      (node (ref "C31") (pin "-") (pinfunction "-_-") (pintype "passive"))
      (node (ref "C33") (pin "-") (pinfunction "-_-") (pintype "passive"))
      (node (ref "CR8") (pin "CATHODE") (pinfunction "CATHODE_CATHODE") (pintype "passive"))
      (node (ref "LED4") (pin "C") (pinfunction "C_C") (pintype "passive"))
      (node (ref "Q28") (pin "2") (pinfunction "D_2") (pintype "passive"))
      (node (ref "Q28") (pin "4") (pinfunction "D_4") (pintype "passive"))
      (node (ref "Q28") (pin "P$1") (pinfunction "D_P$1") (pintype "passive"))
      (node (ref "Q28") (pin "P$10") (pinfunction "D_P$10") (pintype "passive"))
      (node (ref "Q28") (pin "P$11") (pinfunction "D_P$11") (pintype "passive"))
      (node (ref "Q28") (pin "P$12") (pinfunction "D_P$12") (pintype "passive"))
      (node (ref "Q28") (pin "P$13") (pinfunction "D_P$13") (pintype "passive"))
      (node (ref "Q28") (pin "P$14") (pinfunction "D_P$14") (pintype "passive"))
      (node (ref "Q28") (pin "P$15") (pinfunction "D_P$15") (pintype "passive"))
      (node (ref "Q28") (pin "P$16") (pinfunction "D_P$16") (pintype "passive"))
      (node (ref "Q28") (pin "P$17") (pinfunction "D_P$17") (pintype "passive"))
      (node (ref "Q28") (pin "P$18") (pinfunction "D_P$18") (pintype "passive"))
      (node (ref "Q28") (pin "P$19") (pinfunction "D_P$19") (pintype "passive"))
      (node (ref "Q28") (pin "P$2") (pinfunction "D_P$2") (pintype "passive"))
      (node (ref "Q28") (pin "P$20") (pinfunction "D_P$20") (pintype "passive"))
      (node (ref "Q28") (pin "P$21") (pinfunction "D_P$21") (pintype "passive"))
      (node (ref "Q28") (pin "P$22") (pinfunction "D_P$22") (pintype "passive"))
      (node (ref "Q28") (pin "P$23") (pinfunction "D_P$23") (pintype "passive"))
      (node (ref "Q28") (pin "P$24") (pinfunction "D_P$24") (pintype "passive"))
      (node (ref "Q28") (pin "P$25") (pinfunction "D_P$25") (pintype "passive"))
      (node (ref "Q28") (pin "P$26") (pinfunction "D_P$26") (pintype "passive"))
      (node (ref "Q28") (pin "P$27") (pinfunction "D_P$27") (pintype "passive"))
      (node (ref "Q28") (pin "P$28") (pinfunction "D_P$28") (pintype "passive"))
      (node (ref "Q28") (pin "P$29") (pinfunction "D_P$29") (pintype "passive"))
      (node (ref "Q28") (pin "P$3") (pinfunction "D_P$3") (pintype "passive"))
      (node (ref "Q28") (pin "P$30") (pinfunction "D_P$30") (pintype "passive"))
      (node (ref "Q28") (pin "P$31") (pinfunction "D_P$31") (pintype "passive"))
      (node (ref "Q28") (pin "P$32") (pinfunction "D_P$32") (pintype "passive"))
      (node (ref "Q28") (pin "P$33") (pinfunction "D_P$33") (pintype "passive"))
      (node (ref "Q28") (pin "P$34") (pinfunction "D_P$34") (pintype "passive"))
      (node (ref "Q28") (pin "P$35") (pinfunction "D_P$35") (pintype "passive"))
      (node (ref "Q28") (pin "P$36") (pinfunction "D_P$36") (pintype "passive"))
      (node (ref "Q28") (pin "P$37") (pinfunction "D_P$37") (pintype "passive"))
      (node (ref "Q28") (pin "P$38") (pinfunction "D_P$38") (pintype "passive"))
      (node (ref "Q28") (pin "P$39") (pinfunction "D_P$39") (pintype "passive"))
      (node (ref "Q28") (pin "P$4") (pinfunction "D_P$4") (pintype "passive"))
      (node (ref "Q28") (pin "P$40") (pinfunction "D_P$40") (pintype "passive"))
      (node (ref "Q28") (pin "P$41") (pinfunction "D_P$41") (pintype "passive"))
      (node (ref "Q28") (pin "P$42") (pinfunction "D_P$42") (pintype "passive"))
      (node (ref "Q28") (pin "P$43") (pinfunction "D_P$43") (pintype "passive"))
      (node (ref "Q28") (pin "P$44") (pinfunction "D_P$44") (pintype "passive"))
      (node (ref "Q28") (pin "P$45") (pinfunction "D_P$45") (pintype "passive"))
      (node (ref "Q28") (pin "P$46") (pinfunction "D_P$46") (pintype "passive"))
      (node (ref "Q28") (pin "P$47") (pinfunction "D_P$47") (pintype "passive"))
      (node (ref "Q28") (pin "P$48") (pinfunction "D_P$48") (pintype "passive"))
      (node (ref "Q28") (pin "P$49") (pinfunction "D_P$49") (pintype "passive"))
      (node (ref "Q28") (pin "P$5") (pinfunction "D_P$5") (pintype "passive"))
      (node (ref "Q28") (pin "P$50") (pinfunction "D_P$50") (pintype "passive"))
      (node (ref "Q28") (pin "P$51") (pinfunction "D_P$51") (pintype "passive"))
      (node (ref "Q28") (pin "P$52") (pinfunction "D_P$52") (pintype "passive"))
      (node (ref "Q28") (pin "P$53") (pinfunction "D_P$53") (pintype "passive"))
      (node (ref "Q28") (pin "P$54") (pinfunction "D_P$54") (pintype "passive"))
      (node (ref "Q28") (pin "P$55") (pinfunction "D_P$55") (pintype "passive"))
      (node (ref "Q28") (pin "P$56") (pinfunction "D_P$56") (pintype "passive"))
      (node (ref "Q28") (pin "P$57") (pinfunction "D_P$57") (pintype "passive"))
      (node (ref "Q28") (pin "P$58") (pinfunction "D_P$58") (pintype "passive"))
      (node (ref "Q28") (pin "P$59") (pinfunction "D_P$59") (pintype "passive"))
      (node (ref "Q28") (pin "P$6") (pinfunction "D_P$6") (pintype "passive"))
      (node (ref "Q28") (pin "P$60") (pinfunction "D_P$60") (pintype "passive"))
      (node (ref "Q28") (pin "P$61") (pinfunction "D_P$61") (pintype "passive"))
      (node (ref "Q28") (pin "P$62") (pinfunction "D_P$62") (pintype "passive"))
      (node (ref "Q28") (pin "P$63") (pinfunction "D_P$63") (pintype "passive"))
      (node (ref "Q28") (pin "P$7") (pinfunction "D_P$7") (pintype "passive"))
      (node (ref "Q28") (pin "P$8") (pinfunction "D_P$8") (pintype "passive"))
      (node (ref "Q28") (pin "P$9") (pinfunction "D_P$9") (pintype "passive"))
      (node (ref "R13") (pin "2") (pinfunction "2_2") (pintype "passive"))
      (node (ref "TP8") (pin "TP") (pinfunction "TP_TP") (pintype "input"))
    )
    (net (code "13") (name "/V2+") (class "Default")
      (node (ref "C21") (pin "+") (pinfunction "+_+") (pintype "passive"))
      (node (ref "C23") (pin "+") (pinfunction "+_+") (pintype "passive"))
      (node (ref "C27") (pin "1") (pinfunction "1_1") (pintype "passive"))
      (node (ref "CR10") (pin "ANODE") (pinfunction "ANODE_ANODE") (pintype "passive"))
      (node (ref "LED1") (pin "A") (pinfunction "A_A") (pintype "passive"))
      (node (ref "Q23") (pin "2") (pinfunction "D_2") (pintype "passive"))
      (node (ref "Q23") (pin "4") (pinfunction "D_4") (pintype "passive"))
      (node (ref "Q23") (pin "P$1") (pinfunction "D_P$1") (pintype "passive"))
      (node (ref "Q23") (pin "P$10") (pinfunction "D_P$10") (pintype "passive"))
      (node (ref "Q23") (pin "P$11") (pinfunction "D_P$11") (pintype "passive"))
      (node (ref "Q23") (pin "P$12") (pinfunction "D_P$12") (pintype "passive"))
      (node (ref "Q23") (pin "P$13") (pinfunction "D_P$13") (pintype "passive"))
      (node (ref "Q23") (pin "P$14") (pinfunction "D_P$14") (pintype "passive"))
      (node (ref "Q23") (pin "P$15") (pinfunction "D_P$15") (pintype "passive"))
      (node (ref "Q23") (pin "P$16") (pinfunction "D_P$16") (pintype "passive"))
      (node (ref "Q23") (pin "P$17") (pinfunction "D_P$17") (pintype "passive"))
      (node (ref "Q23") (pin "P$18") (pinfunction "D_P$18") (pintype "passive"))
      (node (ref "Q23") (pin "P$19") (pinfunction "D_P$19") (pintype "passive"))
      (node (ref "Q23") (pin "P$2") (pinfunction "D_P$2") (pintype "passive"))
      (node (ref "Q23") (pin "P$20") (pinfunction "D_P$20") (pintype "passive"))
      (node (ref "Q23") (pin "P$21") (pinfunction "D_P$21") (pintype "passive"))
      (node (ref "Q23") (pin "P$22") (pinfunction "D_P$22") (pintype "passive"))
      (node (ref "Q23") (pin "P$23") (pinfunction "D_P$23") (pintype "passive"))
      (node (ref "Q23") (pin "P$24") (pinfunction "D_P$24") (pintype "passive"))
      (node (ref "Q23") (pin "P$25") (pinfunction "D_P$25") (pintype "passive"))
      (node (ref "Q23") (pin "P$26") (pinfunction "D_P$26") (pintype "passive"))
      (node (ref "Q23") (pin "P$27") (pinfunction "D_P$27") (pintype "passive"))
      (node (ref "Q23") (pin "P$28") (pinfunction "D_P$28") (pintype "passive"))
      (node (ref "Q23") (pin "P$29") (pinfunction "D_P$29") (pintype "passive"))
      (node (ref "Q23") (pin "P$3") (pinfunction "D_P$3") (pintype "passive"))
      (node (ref "Q23") (pin "P$30") (pinfunction "D_P$30") (pintype "passive"))
      (node (ref "Q23") (pin "P$31") (pinfunction "D_P$31") (pintype "passive"))
      (node (ref "Q23") (pin "P$32") (pinfunction "D_P$32") (pintype "passive"))
      (node (ref "Q23") (pin "P$33") (pinfunction "D_P$33") (pintype "passive"))
      (node (ref "Q23") (pin "P$34") (pinfunction "D_P$34") (pintype "passive"))
      (node (ref "Q23") (pin "P$35") (pinfunction "D_P$35") (pintype "passive"))
      (node (ref "Q23") (pin "P$36") (pinfunction "D_P$36") (pintype "passive"))
      (node (ref "Q23") (pin "P$37") (pinfunction "D_P$37") (pintype "passive"))
      (node (ref "Q23") (pin "P$38") (pinfunction "D_P$38") (pintype "passive"))
      (node (ref "Q23") (pin "P$39") (pinfunction "D_P$39") (pintype "passive"))
      (node (ref "Q23") (pin "P$4") (pinfunction "D_P$4") (pintype "passive"))
      (node (ref "Q23") (pin "P$40") (pinfunction "D_P$40") (pintype "passive"))
      (node (ref "Q23") (pin "P$41") (pinfunction "D_P$41") (pintype "passive"))
      (node (ref "Q23") (pin "P$42") (pinfunction "D_P$42") (pintype "passive"))
      (node (ref "Q23") (pin "P$43") (pinfunction "D_P$43") (pintype "passive"))
      (node (ref "Q23") (pin "P$44") (pinfunction "D_P$44") (pintype "passive"))
      (node (ref "Q23") (pin "P$45") (pinfunction "D_P$45") (pintype "passive"))
      (node (ref "Q23") (pin "P$46") (pinfunction "D_P$46") (pintype "passive"))
      (node (ref "Q23") (pin "P$47") (pinfunction "D_P$47") (pintype "passive"))
      (node (ref "Q23") (pin "P$48") (pinfunction "D_P$48") (pintype "passive"))
      (node (ref "Q23") (pin "P$49") (pinfunction "D_P$49") (pintype "passive"))
      (node (ref "Q23") (pin "P$5") (pinfunction "D_P$5") (pintype "passive"))
      (node (ref "Q23") (pin "P$50") (pinfunction "D_P$50") (pintype "passive"))
      (node (ref "Q23") (pin "P$51") (pinfunction "D_P$51") (pintype "passive"))
      (node (ref "Q23") (pin "P$52") (pinfunction "D_P$52") (pintype "passive"))
      (node (ref "Q23") (pin "P$53") (pinfunction "D_P$53") (pintype "passive"))
      (node (ref "Q23") (pin "P$54") (pinfunction "D_P$54") (pintype "passive"))
      (node (ref "Q23") (pin "P$55") (pinfunction "D_P$55") (pintype "passive"))
      (node (ref "Q23") (pin "P$56") (pinfunction "D_P$56") (pintype "passive"))
      (node (ref "Q23") (pin "P$57") (pinfunction "D_P$57") (pintype "passive"))
      (node (ref "Q23") (pin "P$58") (pinfunction "D_P$58") (pintype "passive"))
      (node (ref "Q23") (pin "P$59") (pinfunction "D_P$59") (pintype "passive"))
      (node (ref "Q23") (pin "P$6") (pinfunction "D_P$6") (pintype "passive"))
      (node (ref "Q23") (pin "P$60") (pinfunction "D_P$60") (pintype "passive"))
      (node (ref "Q23") (pin "P$61") (pinfunction "D_P$61") (pintype "passive"))
      (node (ref "Q23") (pin "P$62") (pinfunction "D_P$62") (pintype "passive"))
      (node (ref "Q23") (pin "P$63") (pinfunction "D_P$63") (pintype "passive"))
      (node (ref "Q23") (pin "P$7") (pinfunction "D_P$7") (pintype "passive"))
      (node (ref "Q23") (pin "P$8") (pinfunction "D_P$8") (pintype "passive"))
      (node (ref "Q23") (pin "P$9") (pinfunction "D_P$9") (pintype "passive"))
      (node (ref "R28") (pin "2") (pinfunction "2_2") (pintype "passive"))
      (node (ref "TP3") (pin "TP") (pinfunction "TP_TP") (pintype "input"))
    )
    (net (code "14") (name "/V2-") (class "Default")
      (node (ref "C22") (pin "-") (pinfunction "-_-") (pintype "passive"))
      (node (ref "C24") (pin "-") (pinfunction "-_-") (pintype "passive"))
      (node (ref "C28") (pin "2") (pinfunction "2_2") (pintype "passive"))
      (node (ref "CR9") (pin "CATHODE") (pinfunction "CATHODE_CATHODE") (pintype "passive"))
      (node (ref "LED2") (pin "C") (pinfunction "C_C") (pintype "passive"))
      (node (ref "Q24") (pin "2") (pinfunction "D_2") (pintype "passive"))
      (node (ref "Q24") (pin "4") (pinfunction "D_4") (pintype "passive"))
      (node (ref "Q24") (pin "P$1") (pinfunction "D_P$1") (pintype "passive"))
      (node (ref "Q24") (pin "P$10") (pinfunction "D_P$10") (pintype "passive"))
      (node (ref "Q24") (pin "P$11") (pinfunction "D_P$11") (pintype "passive"))
      (node (ref "Q24") (pin "P$12") (pinfunction "D_P$12") (pintype "passive"))
      (node (ref "Q24") (pin "P$13") (pinfunction "D_P$13") (pintype "passive"))
      (node (ref "Q24") (pin "P$14") (pinfunction "D_P$14") (pintype "passive"))
      (node (ref "Q24") (pin "P$15") (pinfunction "D_P$15") (pintype "passive"))
      (node (ref "Q24") (pin "P$16") (pinfunction "D_P$16") (pintype "passive"))
      (node (ref "Q24") (pin "P$17") (pinfunction "D_P$17") (pintype "passive"))
      (node (ref "Q24") (pin "P$18") (pinfunction "D_P$18") (pintype "passive"))
      (node (ref "Q24") (pin "P$19") (pinfunction "D_P$19") (pintype "passive"))
      (node (ref "Q24") (pin "P$2") (pinfunction "D_P$2") (pintype "passive"))
      (node (ref "Q24") (pin "P$20") (pinfunction "D_P$20") (pintype "passive"))
      (node (ref "Q24") (pin "P$21") (pinfunction "D_P$21") (pintype "passive"))
      (node (ref "Q24") (pin "P$22") (pinfunction "D_P$22") (pintype "passive"))
      (node (ref "Q24") (pin "P$23") (pinfunction "D_P$23") (pintype "passive"))
      (node (ref "Q24") (pin "P$24") (pinfunction "D_P$24") (pintype "passive"))
      (node (ref "Q24") (pin "P$25") (pinfunction "D_P$25") (pintype "passive"))
      (node (ref "Q24") (pin "P$26") (pinfunction "D_P$26") (pintype "passive"))
      (node (ref "Q24") (pin "P$27") (pinfunction "D_P$27") (pintype "passive"))
      (node (ref "Q24") (pin "P$28") (pinfunction "D_P$28") (pintype "passive"))
      (node (ref "Q24") (pin "P$29") (pinfunction "D_P$29") (pintype "passive"))
      (node (ref "Q24") (pin "P$3") (pinfunction "D_P$3") (pintype "passive"))
      (node (ref "Q24") (pin "P$30") (pinfunction "D_P$30") (pintype "passive"))
      (node (ref "Q24") (pin "P$31") (pinfunction "D_P$31") (pintype "passive"))
      (node (ref "Q24") (pin "P$32") (pinfunction "D_P$32") (pintype "passive"))
      (node (ref "Q24") (pin "P$33") (pinfunction "D_P$33") (pintype "passive"))
      (node (ref "Q24") (pin "P$34") (pinfunction "D_P$34") (pintype "passive"))
      (node (ref "Q24") (pin "P$35") (pinfunction "D_P$35") (pintype "passive"))
      (node (ref "Q24") (pin "P$36") (pinfunction "D_P$36") (pintype "passive"))
      (node (ref "Q24") (pin "P$37") (pinfunction "D_P$37") (pintype "passive"))
      (node (ref "Q24") (pin "P$38") (pinfunction "D_P$38") (pintype "passive"))
      (node (ref "Q24") (pin "P$39") (pinfunction "D_P$39") (pintype "passive"))
      (node (ref "Q24") (pin "P$4") (pinfunction "D_P$4") (pintype "passive"))
      (node (ref "Q24") (pin "P$40") (pinfunction "D_P$40") (pintype "passive"))
      (node (ref "Q24") (pin "P$41") (pinfunction "D_P$41") (pintype "passive"))
      (node (ref "Q24") (pin "P$42") (pinfunction "D_P$42") (pintype "passive"))
      (node (ref "Q24") (pin "P$43") (pinfunction "D_P$43") (pintype "passive"))
      (node (ref "Q24") (pin "P$44") (pinfunction "D_P$44") (pintype "passive"))
      (node (ref "Q24") (pin "P$45") (pinfunction "D_P$45") (pintype "passive"))
      (node (ref "Q24") (pin "P$46") (pinfunction "D_P$46") (pintype "passive"))
      (node (ref "Q24") (pin "P$47") (pinfunction "D_P$47") (pintype "passive"))
      (node (ref "Q24") (pin "P$48") (pinfunction "D_P$48") (pintype "passive"))
      (node (ref "Q24") (pin "P$49") (pinfunction "D_P$49") (pintype "passive"))
      (node (ref "Q24") (pin "P$5") (pinfunction "D_P$5") (pintype "passive"))
      (node (ref "Q24") (pin "P$50") (pinfunction "D_P$50") (pintype "passive"))
      (node (ref "Q24") (pin "P$51") (pinfunction "D_P$51") (pintype "passive"))
      (node (ref "Q24") (pin "P$52") (pinfunction "D_P$52") (pintype "passive"))
      (node (ref "Q24") (pin "P$53") (pinfunction "D_P$53") (pintype "passive"))
      (node (ref "Q24") (pin "P$54") (pinfunction "D_P$54") (pintype "passive"))
      (node (ref "Q24") (pin "P$55") (pinfunction "D_P$55") (pintype "passive"))
      (node (ref "Q24") (pin "P$56") (pinfunction "D_P$56") (pintype "passive"))
      (node (ref "Q24") (pin "P$57") (pinfunction "D_P$57") (pintype "passive"))
      (node (ref "Q24") (pin "P$58") (pinfunction "D_P$58") (pintype "passive"))
      (node (ref "Q24") (pin "P$59") (pinfunction "D_P$59") (pintype "passive"))
      (node (ref "Q24") (pin "P$6") (pinfunction "D_P$6") (pintype "passive"))
      (node (ref "Q24") (pin "P$60") (pinfunction "D_P$60") (pintype "passive"))
      (node (ref "Q24") (pin "P$61") (pinfunction "D_P$61") (pintype "passive"))
      (node (ref "Q24") (pin "P$62") (pinfunction "D_P$62") (pintype "passive"))
      (node (ref "Q24") (pin "P$63") (pinfunction "D_P$63") (pintype "passive"))
      (node (ref "Q24") (pin "P$7") (pinfunction "D_P$7") (pintype "passive"))
      (node (ref "Q24") (pin "P$8") (pinfunction "D_P$8") (pintype "passive"))
      (node (ref "Q24") (pin "P$9") (pinfunction "D_P$9") (pintype "passive"))
      (node (ref "R29") (pin "2") (pinfunction "2_2") (pintype "passive"))
      (node (ref "TP4") (pin "TP") (pinfunction "TP_TP") (pintype "input"))
    )
    (net (code "15") (name "GND") (class "Default")
      (node (ref "C15") (pin "2") (pinfunction "2_2") (pintype "passive"))
      (node (ref "C16") (pin "2") (pinfunction "2_2") (pintype "passive"))
      (node (ref "C17") (pin "1") (pinfunction "1_1") (pintype "passive"))
      (node (ref "C18") (pin "1") (pinfunction "1_1") (pintype "passive"))
      (node (ref "C19") (pin "+") (pinfunction "+_+") (pintype "passive"))
      (node (ref "C20") (pin "-") (pinfunction "-_-") (pintype "passive"))
      (node (ref "R20") (pin "1") (pinfunction "1_1") (pintype "passive"))
      (node (ref "R21") (pin "2") (pinfunction "2_2") (pintype "passive"))
      (node (ref "R23") (pin "1") (pinfunction "1_1") (pintype "passive"))
      (node (ref "R24") (pin "2") (pinfunction "2_2") (pintype "passive"))
      (node (ref "R41") (pin "2") (pinfunction "2_2") (pintype "passive"))
      (node (ref "R51") (pin "2") (pinfunction "2_2") (pintype "passive"))
      (node (ref "R52") (pin "2") (pinfunction "2_2") (pintype "passive"))
      (node (ref "SJ1") (pin "P$2") (pinfunction "2_P$2") (pintype "passive"))
      (node (ref "SJ2") (pin "P$2") (pinfunction "2_P$2") (pintype "passive"))
      (node (ref "TP13") (pin "TP") (pinfunction "TP_TP") (pintype "input"))
      (node (ref "U$18") (pin "P$1") (pinfunction "P$1_P$1") (pintype "bidirectional"))
      (node (ref "U$18") (pin "P$2") (pinfunction "P$1_P$2") (pintype "bidirectional"))
      (node (ref "U$18") (pin "P$3") (pinfunction "P$1_P$3") (pintype "bidirectional"))
      (node (ref "U$18") (pin "P$4") (pinfunction "P$1_P$4") (pintype "bidirectional"))
      (node (ref "U$18") (pin "P$5") (pinfunction "P$1_P$5") (pintype "bidirectional"))
      (node (ref "U$18") (pin "P$6") (pinfunction "P$1_P$6") (pintype "bidirectional"))
      (node (ref "U$18") (pin "P$7") (pinfunction "P$1_P$7") (pintype "bidirectional"))
      (node (ref "U$18") (pin "P$8") (pinfunction "P$1_P$8") (pintype "bidirectional"))
    )
    (net (code "16") (name "Net-(C8-Pad1)") (class "Default")
      (node (ref "C8") (pin "1") (pinfunction "1_1") (pintype "passive"))
      (node (ref "CR10") (pin "CATHODE") (pinfunction "CATHODE_CATHODE") (pintype "passive"))
      (node (ref "D9") (pin "C") (pinfunction "C_C") (pintype "passive"))
      (node (ref "R28") (pin "1") (pinfunction "1_1") (pintype "passive"))
      (node (ref "R32") (pin "2") (pinfunction "2_2") (pintype "passive"))
    )
    (net (code "17") (name "Net-(C8-Pad2)") (class "Default")
      (node (ref "C8") (pin "2") (pinfunction "2_2") (pintype "passive"))
      (node (ref "CR9") (pin "ANODE") (pinfunction "ANODE_ANODE") (pintype "passive"))
      (node (ref "D10") (pin "A") (pinfunction "A_A") (pintype "passive"))
      (node (ref "R29") (pin "1") (pinfunction "1_1") (pintype "passive"))
      (node (ref "R33") (pin "2") (pinfunction "2_2") (pintype "passive"))
    )
    (net (code "18") (name "Net-(C9-Pad1)") (class "Default")
      (node (ref "C9") (pin "1") (pinfunction "1_1") (pintype "passive"))
      (node (ref "CR7") (pin "ANODE") (pinfunction "ANODE_ANODE") (pintype "passive"))
      (node (ref "D3") (pin "C") (pinfunction "C_C") (pintype "passive"))
      (node (ref "R22") (pin "2") (pinfunction "2_2") (pintype "passive"))
      (node (ref "R6") (pin "1") (pinfunction "1_1") (pintype "passive"))
    )
    (net (code "19") (name "Net-(C9-Pad2)") (class "Default")
      (node (ref "C9") (pin "2") (pinfunction "2_2") (pintype "passive"))
      (node (ref "CR8") (pin "ANODE") (pinfunction "ANODE_ANODE") (pintype "passive"))
      (node (ref "D4") (pin "A") (pinfunction "A_A") (pintype "passive"))
      (node (ref "R13") (pin "1") (pinfunction "1_1") (pintype "passive"))
      (node (ref "R30") (pin "2") (pinfunction "2_2") (pintype "passive"))
    )
    (net (code "20") (name "Net-(LED1-PadC)") (class "Default")
      (node (ref "LED1") (pin "C") (pinfunction "C_C") (pintype "passive"))
      (node (ref "R53") (pin "2") (pinfunction "2_2") (pintype "passive"))
    )
    (net (code "21") (name "Net-(LED2-PadA)") (class "Default")
      (node (ref "LED2") (pin "A") (pinfunction "A_A") (pintype "passive"))
      (node (ref "R54") (pin "1") (pinfunction "1_1") (pintype "passive"))
    )
    (net (code "22") (name "Net-(LED3-PadC)") (class "Default")
      (node (ref "LED3") (pin "C") (pinfunction "C_C") (pintype "passive"))
      (node (ref "R49") (pin "2") (pinfunction "2_2") (pintype "passive"))
    )
    (net (code "23") (name "Net-(LED4-PadA)") (class "Default")
      (node (ref "LED4") (pin "A") (pinfunction "A_A") (pintype "passive"))
      (node (ref "R50") (pin "1") (pinfunction "1_1") (pintype "passive"))
    )
    (net (code "24") (name "Net-(LED5-PadC)") (class "Default")
      (node (ref "LED5") (pin "C") (pinfunction "C_C") (pintype "passive"))
      (node (ref "R51") (pin "1") (pinfunction "1_1") (pintype "passive"))
    )
    (net (code "25") (name "Net-(LED6-PadA)") (class "Default")
      (node (ref "LED6") (pin "A") (pinfunction "A_A") (pintype "passive"))
      (node (ref "R52") (pin "1") (pinfunction "1_1") (pintype "passive"))
    )
    (net (code "26") (name "Net-(Q21-G)") (class "Default")
      (node (ref "C3") (pin "1") (pinfunction "1_1") (pintype "passive"))
      (node (ref "C7") (pin "1") (pinfunction "1_1") (pintype "passive"))
      (node (ref "Q21") (pin "1") (pinfunction "G_1") (pintype "passive"))
      (node (ref "R23") (pin "2") (pinfunction "2_2") (pintype "passive"))
      (node (ref "R25") (pin "2") (pinfunction "2_2") (pintype "passive"))
      (node (ref "U$12") (pin "6") (pinfunction "C_6") (pintype "passive"))
      (node (ref "U$4") (pin "5") (pinfunction "C1_5") (pintype "passive"))
    )
    (net (code "27") (name "Net-(Q21-S)") (class "Default")
      (node (ref "Q21") (pin "3") (pinfunction "S_3") (pintype "passive"))
      (node (ref "R34") (pin "1") (pinfunction "1_1") (pintype "passive"))
    )
    (net (code "28") (name "Net-(Q22-G)") (class "Default")
      (node (ref "C5") (pin "1") (pinfunction "1_1") (pintype "passive"))
      (node (ref "C7") (pin "2") (pinfunction "2_2") (pintype "passive"))
      (node (ref "Q22") (pin "1") (pinfunction "G_1") (pintype "passive"))
      (node (ref "R24") (pin "1") (pinfunction "1_1") (pintype "passive"))
      (node (ref "R26") (pin "1") (pinfunction "1_1") (pintype "passive"))
      (node (ref "U$4") (pin "4") (pinfunction "C2_4") (pintype "passive"))
      (node (ref "U$8") (pin "6") (pinfunction "C_6") (pintype "passive"))
    )
    (net (code "29") (name "Net-(Q22-S)") (class "Default")
      (node (ref "Q22") (pin "3") (pinfunction "S_3") (pintype "passive"))
      (node (ref "R35") (pin "2") (pinfunction "2_2") (pintype "passive"))
    )
    (net (code "30") (name "Net-(Q23-G)") (class "Default")
      (node (ref "Q23") (pin "1") (pinfunction "G_1") (pintype "passive"))
      (node (ref "R32") (pin "1") (pinfunction "1_1") (pintype "passive"))
    )
    (net (code "31") (name "Net-(Q23-S)") (class "Default")
      (node (ref "Q21") (pin "2") (pinfunction "D_2") (pintype "passive"))
      (node (ref "Q21") (pin "4") (pinfunction "D_4") (pintype "passive"))
      (node (ref "Q21") (pin "P$1") (pinfunction "D_P$1") (pintype "passive"))
      (node (ref "Q21") (pin "P$10") (pinfunction "D_P$10") (pintype "passive"))
      (node (ref "Q21") (pin "P$11") (pinfunction "D_P$11") (pintype "passive"))
      (node (ref "Q21") (pin "P$12") (pinfunction "D_P$12") (pintype "passive"))
      (node (ref "Q21") (pin "P$13") (pinfunction "D_P$13") (pintype "passive"))
      (node (ref "Q21") (pin "P$14") (pinfunction "D_P$14") (pintype "passive"))
      (node (ref "Q21") (pin "P$15") (pinfunction "D_P$15") (pintype "passive"))
      (node (ref "Q21") (pin "P$16") (pinfunction "D_P$16") (pintype "passive"))
      (node (ref "Q21") (pin "P$17") (pinfunction "D_P$17") (pintype "passive"))
      (node (ref "Q21") (pin "P$18") (pinfunction "D_P$18") (pintype "passive"))
      (node (ref "Q21") (pin "P$19") (pinfunction "D_P$19") (pintype "passive"))
      (node (ref "Q21") (pin "P$2") (pinfunction "D_P$2") (pintype "passive"))
      (node (ref "Q21") (pin "P$20") (pinfunction "D_P$20") (pintype "passive"))
      (node (ref "Q21") (pin "P$21") (pinfunction "D_P$21") (pintype "passive"))
      (node (ref "Q21") (pin "P$22") (pinfunction "D_P$22") (pintype "passive"))
      (node (ref "Q21") (pin "P$23") (pinfunction "D_P$23") (pintype "passive"))
      (node (ref "Q21") (pin "P$24") (pinfunction "D_P$24") (pintype "passive"))
      (node (ref "Q21") (pin "P$25") (pinfunction "D_P$25") (pintype "passive"))
      (node (ref "Q21") (pin "P$26") (pinfunction "D_P$26") (pintype "passive"))
      (node (ref "Q21") (pin "P$27") (pinfunction "D_P$27") (pintype "passive"))
      (node (ref "Q21") (pin "P$28") (pinfunction "D_P$28") (pintype "passive"))
      (node (ref "Q21") (pin "P$29") (pinfunction "D_P$29") (pintype "passive"))
      (node (ref "Q21") (pin "P$3") (pinfunction "D_P$3") (pintype "passive"))
      (node (ref "Q21") (pin "P$30") (pinfunction "D_P$30") (pintype "passive"))
      (node (ref "Q21") (pin "P$31") (pinfunction "D_P$31") (pintype "passive"))
      (node (ref "Q21") (pin "P$32") (pinfunction "D_P$32") (pintype "passive"))
      (node (ref "Q21") (pin "P$33") (pinfunction "D_P$33") (pintype "passive"))
      (node (ref "Q21") (pin "P$34") (pinfunction "D_P$34") (pintype "passive"))
      (node (ref "Q21") (pin "P$35") (pinfunction "D_P$35") (pintype "passive"))
      (node (ref "Q21") (pin "P$36") (pinfunction "D_P$36") (pintype "passive"))
      (node (ref "Q21") (pin "P$37") (pinfunction "D_P$37") (pintype "passive"))
      (node (ref "Q21") (pin "P$38") (pinfunction "D_P$38") (pintype "passive"))
      (node (ref "Q21") (pin "P$39") (pinfunction "D_P$39") (pintype "passive"))
      (node (ref "Q21") (pin "P$4") (pinfunction "D_P$4") (pintype "passive"))
      (node (ref "Q21") (pin "P$40") (pinfunction "D_P$40") (pintype "passive"))
      (node (ref "Q21") (pin "P$41") (pinfunction "D_P$41") (pintype "passive"))
      (node (ref "Q21") (pin "P$42") (pinfunction "D_P$42") (pintype "passive"))
      (node (ref "Q21") (pin "P$43") (pinfunction "D_P$43") (pintype "passive"))
      (node (ref "Q21") (pin "P$44") (pinfunction "D_P$44") (pintype "passive"))
      (node (ref "Q21") (pin "P$45") (pinfunction "D_P$45") (pintype "passive"))
      (node (ref "Q21") (pin "P$46") (pinfunction "D_P$46") (pintype "passive"))
      (node (ref "Q21") (pin "P$47") (pinfunction "D_P$47") (pintype "passive"))
      (node (ref "Q21") (pin "P$48") (pinfunction "D_P$48") (pintype "passive"))
      (node (ref "Q21") (pin "P$49") (pinfunction "D_P$49") (pintype "passive"))
      (node (ref "Q21") (pin "P$5") (pinfunction "D_P$5") (pintype "passive"))
      (node (ref "Q21") (pin "P$50") (pinfunction "D_P$50") (pintype "passive"))
      (node (ref "Q21") (pin "P$51") (pinfunction "D_P$51") (pintype "passive"))
      (node (ref "Q21") (pin "P$52") (pinfunction "D_P$52") (pintype "passive"))
      (node (ref "Q21") (pin "P$53") (pinfunction "D_P$53") (pintype "passive"))
      (node (ref "Q21") (pin "P$54") (pinfunction "D_P$54") (pintype "passive"))
      (node (ref "Q21") (pin "P$55") (pinfunction "D_P$55") (pintype "passive"))
      (node (ref "Q21") (pin "P$56") (pinfunction "D_P$56") (pintype "passive"))
      (node (ref "Q21") (pin "P$57") (pinfunction "D_P$57") (pintype "passive"))
      (node (ref "Q21") (pin "P$58") (pinfunction "D_P$58") (pintype "passive"))
      (node (ref "Q21") (pin "P$59") (pinfunction "D_P$59") (pintype "passive"))
      (node (ref "Q21") (pin "P$6") (pinfunction "D_P$6") (pintype "passive"))
      (node (ref "Q21") (pin "P$60") (pinfunction "D_P$60") (pintype "passive"))
      (node (ref "Q21") (pin "P$61") (pinfunction "D_P$61") (pintype "passive"))
      (node (ref "Q21") (pin "P$62") (pinfunction "D_P$62") (pintype "passive"))
      (node (ref "Q21") (pin "P$63") (pinfunction "D_P$63") (pintype "passive"))
      (node (ref "Q21") (pin "P$7") (pinfunction "D_P$7") (pintype "passive"))
      (node (ref "Q21") (pin "P$8") (pinfunction "D_P$8") (pintype "passive"))
      (node (ref "Q21") (pin "P$9") (pinfunction "D_P$9") (pintype "passive"))
      (node (ref "Q23") (pin "3") (pinfunction "S_3") (pintype "passive"))
    )
    (net (code "32") (name "Net-(Q24-G)") (class "Default")
      (node (ref "Q24") (pin "1") (pinfunction "G_1") (pintype "passive"))
      (node (ref "R33") (pin "1") (pinfunction "1_1") (pintype "passive"))
    )
    (net (code "33") (name "Net-(Q24-S)") (class "Default")
      (node (ref "Q22") (pin "2") (pinfunction "D_2") (pintype "passive"))
      (node (ref "Q22") (pin "4") (pinfunction "D_4") (pintype "passive"))
      (node (ref "Q22") (pin "P$1") (pinfunction "D_P$1") (pintype "passive"))
      (node (ref "Q22") (pin "P$10") (pinfunction "D_P$10") (pintype "passive"))
      (node (ref "Q22") (pin "P$11") (pinfunction "D_P$11") (pintype "passive"))
      (node (ref "Q22") (pin "P$12") (pinfunction "D_P$12") (pintype "passive"))
      (node (ref "Q22") (pin "P$13") (pinfunction "D_P$13") (pintype "passive"))
      (node (ref "Q22") (pin "P$14") (pinfunction "D_P$14") (pintype "passive"))
      (node (ref "Q22") (pin "P$15") (pinfunction "D_P$15") (pintype "passive"))
      (node (ref "Q22") (pin "P$16") (pinfunction "D_P$16") (pintype "passive"))
      (node (ref "Q22") (pin "P$17") (pinfunction "D_P$17") (pintype "passive"))
      (node (ref "Q22") (pin "P$18") (pinfunction "D_P$18") (pintype "passive"))
      (node (ref "Q22") (pin "P$19") (pinfunction "D_P$19") (pintype "passive"))
      (node (ref "Q22") (pin "P$2") (pinfunction "D_P$2") (pintype "passive"))
      (node (ref "Q22") (pin "P$20") (pinfunction "D_P$20") (pintype "passive"))
      (node (ref "Q22") (pin "P$21") (pinfunction "D_P$21") (pintype "passive"))
      (node (ref "Q22") (pin "P$22") (pinfunction "D_P$22") (pintype "passive"))
      (node (ref "Q22") (pin "P$23") (pinfunction "D_P$23") (pintype "passive"))
      (node (ref "Q22") (pin "P$24") (pinfunction "D_P$24") (pintype "passive"))
      (node (ref "Q22") (pin "P$25") (pinfunction "D_P$25") (pintype "passive"))
      (node (ref "Q22") (pin "P$26") (pinfunction "D_P$26") (pintype "passive"))
      (node (ref "Q22") (pin "P$27") (pinfunction "D_P$27") (pintype "passive"))
      (node (ref "Q22") (pin "P$28") (pinfunction "D_P$28") (pintype "passive"))
      (node (ref "Q22") (pin "P$29") (pinfunction "D_P$29") (pintype "passive"))
      (node (ref "Q22") (pin "P$3") (pinfunction "D_P$3") (pintype "passive"))
      (node (ref "Q22") (pin "P$30") (pinfunction "D_P$30") (pintype "passive"))
      (node (ref "Q22") (pin "P$31") (pinfunction "D_P$31") (pintype "passive"))
      (node (ref "Q22") (pin "P$32") (pinfunction "D_P$32") (pintype "passive"))
      (node (ref "Q22") (pin "P$33") (pinfunction "D_P$33") (pintype "passive"))
      (node (ref "Q22") (pin "P$34") (pinfunction "D_P$34") (pintype "passive"))
      (node (ref "Q22") (pin "P$35") (pinfunction "D_P$35") (pintype "passive"))
      (node (ref "Q22") (pin "P$36") (pinfunction "D_P$36") (pintype "passive"))
      (node (ref "Q22") (pin "P$37") (pinfunction "D_P$37") (pintype "passive"))
      (node (ref "Q22") (pin "P$38") (pinfunction "D_P$38") (pintype "passive"))
      (node (ref "Q22") (pin "P$39") (pinfunction "D_P$39") (pintype "passive"))
      (node (ref "Q22") (pin "P$4") (pinfunction "D_P$4") (pintype "passive"))
      (node (ref "Q22") (pin "P$40") (pinfunction "D_P$40") (pintype "passive"))
      (node (ref "Q22") (pin "P$41") (pinfunction "D_P$41") (pintype "passive"))
      (node (ref "Q22") (pin "P$42") (pinfunction "D_P$42") (pintype "passive"))
      (node (ref "Q22") (pin "P$43") (pinfunction "D_P$43") (pintype "passive"))
      (node (ref "Q22") (pin "P$44") (pinfunction "D_P$44") (pintype "passive"))
      (node (ref "Q22") (pin "P$45") (pinfunction "D_P$45") (pintype "passive"))
      (node (ref "Q22") (pin "P$46") (pinfunction "D_P$46") (pintype "passive"))
      (node (ref "Q22") (pin "P$47") (pinfunction "D_P$47") (pintype "passive"))
      (node (ref "Q22") (pin "P$48") (pinfunction "D_P$48") (pintype "passive"))
      (node (ref "Q22") (pin "P$49") (pinfunction "D_P$49") (pintype "passive"))
      (node (ref "Q22") (pin "P$5") (pinfunction "D_P$5") (pintype "passive"))
      (node (ref "Q22") (pin "P$50") (pinfunction "D_P$50") (pintype "passive"))
      (node (ref "Q22") (pin "P$51") (pinfunction "D_P$51") (pintype "passive"))
      (node (ref "Q22") (pin "P$52") (pinfunction "D_P$52") (pintype "passive"))
      (node (ref "Q22") (pin "P$53") (pinfunction "D_P$53") (pintype "passive"))
      (node (ref "Q22") (pin "P$54") (pinfunction "D_P$54") (pintype "passive"))
      (node (ref "Q22") (pin "P$55") (pinfunction "D_P$55") (pintype "passive"))
      (node (ref "Q22") (pin "P$56") (pinfunction "D_P$56") (pintype "passive"))
      (node (ref "Q22") (pin "P$57") (pinfunction "D_P$57") (pintype "passive"))
      (node (ref "Q22") (pin "P$58") (pinfunction "D_P$58") (pintype "passive"))
      (node (ref "Q22") (pin "P$59") (pinfunction "D_P$59") (pintype "passive"))
      (node (ref "Q22") (pin "P$6") (pinfunction "D_P$6") (pintype "passive"))
      (node (ref "Q22") (pin "P$60") (pinfunction "D_P$60") (pintype "passive"))
      (node (ref "Q22") (pin "P$61") (pinfunction "D_P$61") (pintype "passive"))
      (node (ref "Q22") (pin "P$62") (pinfunction "D_P$62") (pintype "passive"))
      (node (ref "Q22") (pin "P$63") (pinfunction "D_P$63") (pintype "passive"))
      (node (ref "Q22") (pin "P$7") (pinfunction "D_P$7") (pintype "passive"))
      (node (ref "Q22") (pin "P$8") (pinfunction "D_P$8") (pintype "passive"))
      (node (ref "Q22") (pin "P$9") (pinfunction "D_P$9") (pintype "passive"))
      (node (ref "Q24") (pin "3") (pinfunction "S_3") (pintype "passive"))
    )
    (net (code "34") (name "Net-(Q25-G)") (class "Default")
      (node (ref "C2") (pin "1") (pinfunction "1_1") (pintype "passive"))
      (node (ref "C6") (pin "1") (pinfunction "1_1") (pintype "passive"))
      (node (ref "Q25") (pin "1") (pinfunction "G_1") (pintype "passive"))
      (node (ref "R1") (pin "2") (pinfunction "2_2") (pintype "passive"))
      (node (ref "R20") (pin "2") (pinfunction "2_2") (pintype "passive"))
      (node (ref "U$12") (pin "4") (pinfunction "C_4") (pintype "passive"))
      (node (ref "U$16") (pin "5") (pinfunction "C1_5") (pintype "passive"))
    )
    (net (code "35") (name "Net-(Q25-S)") (class "Default")
      (node (ref "Q25") (pin "3") (pinfunction "S_3") (pintype "passive"))
      (node (ref "R31") (pin "1") (pinfunction "1_1") (pintype "passive"))
    )
    (net (code "36") (name "Net-(Q26-G)") (class "Default")
      (node (ref "C4") (pin "1") (pinfunction "1_1") (pintype "passive"))
      (node (ref "C6") (pin "2") (pinfunction "2_2") (pintype "passive"))
      (node (ref "Q26") (pin "1") (pinfunction "G_1") (pintype "passive"))
      (node (ref "R2") (pin "1") (pinfunction "1_1") (pintype "passive"))
      (node (ref "R21") (pin "1") (pinfunction "1_1") (pintype "passive"))
      (node (ref "U$16") (pin "4") (pinfunction "C2_4") (pintype "passive"))
      (node (ref "U$8") (pin "4") (pinfunction "C_4") (pintype "passive"))
    )
    (net (code "37") (name "Net-(Q26-S)") (class "Default")
      (node (ref "Q26") (pin "3") (pinfunction "S_3") (pintype "passive"))
      (node (ref "R36") (pin "2") (pinfunction "2_2") (pintype "passive"))
    )
    (net (code "38") (name "Net-(Q27-G)") (class "Default")
      (node (ref "Q27") (pin "1") (pinfunction "G_1") (pintype "passive"))
      (node (ref "R22") (pin "1") (pinfunction "1_1") (pintype "passive"))
    )
    (net (code "39") (name "Net-(Q27-S)") (class "Default")
      (node (ref "Q25") (pin "2") (pinfunction "D_2") (pintype "passive"))
      (node (ref "Q25") (pin "4") (pinfunction "D_4") (pintype "passive"))
      (node (ref "Q25") (pin "P$1") (pinfunction "D_P$1") (pintype "passive"))
      (node (ref "Q25") (pin "P$10") (pinfunction "D_P$10") (pintype "passive"))
      (node (ref "Q25") (pin "P$11") (pinfunction "D_P$11") (pintype "passive"))
      (node (ref "Q25") (pin "P$12") (pinfunction "D_P$12") (pintype "passive"))
      (node (ref "Q25") (pin "P$13") (pinfunction "D_P$13") (pintype "passive"))
      (node (ref "Q25") (pin "P$14") (pinfunction "D_P$14") (pintype "passive"))
      (node (ref "Q25") (pin "P$15") (pinfunction "D_P$15") (pintype "passive"))
      (node (ref "Q25") (pin "P$16") (pinfunction "D_P$16") (pintype "passive"))
      (node (ref "Q25") (pin "P$17") (pinfunction "D_P$17") (pintype "passive"))
      (node (ref "Q25") (pin "P$18") (pinfunction "D_P$18") (pintype "passive"))
      (node (ref "Q25") (pin "P$19") (pinfunction "D_P$19") (pintype "passive"))
      (node (ref "Q25") (pin "P$2") (pinfunction "D_P$2") (pintype "passive"))
      (node (ref "Q25") (pin "P$20") (pinfunction "D_P$20") (pintype "passive"))
      (node (ref "Q25") (pin "P$21") (pinfunction "D_P$21") (pintype "passive"))
      (node (ref "Q25") (pin "P$22") (pinfunction "D_P$22") (pintype "passive"))
      (node (ref "Q25") (pin "P$23") (pinfunction "D_P$23") (pintype "passive"))
      (node (ref "Q25") (pin "P$24") (pinfunction "D_P$24") (pintype "passive"))
      (node (ref "Q25") (pin "P$25") (pinfunction "D_P$25") (pintype "passive"))
      (node (ref "Q25") (pin "P$26") (pinfunction "D_P$26") (pintype "passive"))
      (node (ref "Q25") (pin "P$27") (pinfunction "D_P$27") (pintype "passive"))
      (node (ref "Q25") (pin "P$28") (pinfunction "D_P$28") (pintype "passive"))
      (node (ref "Q25") (pin "P$29") (pinfunction "D_P$29") (pintype "passive"))
      (node (ref "Q25") (pin "P$3") (pinfunction "D_P$3") (pintype "passive"))
      (node (ref "Q25") (pin "P$30") (pinfunction "D_P$30") (pintype "passive"))
      (node (ref "Q25") (pin "P$31") (pinfunction "D_P$31") (pintype "passive"))
      (node (ref "Q25") (pin "P$32") (pinfunction "D_P$32") (pintype "passive"))
      (node (ref "Q25") (pin "P$33") (pinfunction "D_P$33") (pintype "passive"))
      (node (ref "Q25") (pin "P$34") (pinfunction "D_P$34") (pintype "passive"))
      (node (ref "Q25") (pin "P$35") (pinfunction "D_P$35") (pintype "passive"))
      (node (ref "Q25") (pin "P$36") (pinfunction "D_P$36") (pintype "passive"))
      (node (ref "Q25") (pin "P$37") (pinfunction "D_P$37") (pintype "passive"))
      (node (ref "Q25") (pin "P$38") (pinfunction "D_P$38") (pintype "passive"))
      (node (ref "Q25") (pin "P$39") (pinfunction "D_P$39") (pintype "passive"))
      (node (ref "Q25") (pin "P$4") (pinfunction "D_P$4") (pintype "passive"))
      (node (ref "Q25") (pin "P$40") (pinfunction "D_P$40") (pintype "passive"))
      (node (ref "Q25") (pin "P$41") (pinfunction "D_P$41") (pintype "passive"))
      (node (ref "Q25") (pin "P$42") (pinfunction "D_P$42") (pintype "passive"))
      (node (ref "Q25") (pin "P$43") (pinfunction "D_P$43") (pintype "passive"))
      (node (ref "Q25") (pin "P$44") (pinfunction "D_P$44") (pintype "passive"))
      (node (ref "Q25") (pin "P$45") (pinfunction "D_P$45") (pintype "passive"))
      (node (ref "Q25") (pin "P$46") (pinfunction "D_P$46") (pintype "passive"))
      (node (ref "Q25") (pin "P$47") (pinfunction "D_P$47") (pintype "passive"))
      (node (ref "Q25") (pin "P$48") (pinfunction "D_P$48") (pintype "passive"))
      (node (ref "Q25") (pin "P$49") (pinfunction "D_P$49") (pintype "passive"))
      (node (ref "Q25") (pin "P$5") (pinfunction "D_P$5") (pintype "passive"))
      (node (ref "Q25") (pin "P$50") (pinfunction "D_P$50") (pintype "passive"))
      (node (ref "Q25") (pin "P$51") (pinfunction "D_P$51") (pintype "passive"))
      (node (ref "Q25") (pin "P$52") (pinfunction "D_P$52") (pintype "passive"))
      (node (ref "Q25") (pin "P$53") (pinfunction "D_P$53") (pintype "passive"))
      (node (ref "Q25") (pin "P$54") (pinfunction "D_P$54") (pintype "passive"))
      (node (ref "Q25") (pin "P$55") (pinfunction "D_P$55") (pintype "passive"))
      (node (ref "Q25") (pin "P$56") (pinfunction "D_P$56") (pintype "passive"))
      (node (ref "Q25") (pin "P$57") (pinfunction "D_P$57") (pintype "passive"))
      (node (ref "Q25") (pin "P$58") (pinfunction "D_P$58") (pintype "passive"))
      (node (ref "Q25") (pin "P$59") (pinfunction "D_P$59") (pintype "passive"))
      (node (ref "Q25") (pin "P$6") (pinfunction "D_P$6") (pintype "passive"))
      (node (ref "Q25") (pin "P$60") (pinfunction "D_P$60") (pintype "passive"))
      (node (ref "Q25") (pin "P$61") (pinfunction "D_P$61") (pintype "passive"))
      (node (ref "Q25") (pin "P$62") (pinfunction "D_P$62") (pintype "passive"))
      (node (ref "Q25") (pin "P$63") (pinfunction "D_P$63") (pintype "passive"))
      (node (ref "Q25") (pin "P$7") (pinfunction "D_P$7") (pintype "passive"))
      (node (ref "Q25") (pin "P$8") (pinfunction "D_P$8") (pintype "passive"))
      (node (ref "Q25") (pin "P$9") (pinfunction "D_P$9") (pintype "passive"))
      (node (ref "Q27") (pin "3") (pinfunction "S_3") (pintype "passive"))
    )
    (net (code "40") (name "Net-(Q28-G)") (class "Default")
      (node (ref "Q28") (pin "1") (pinfunction "G_1") (pintype "passive"))
      (node (ref "R30") (pin "1") (pinfunction "1_1") (pintype "passive"))
    )
    (net (code "41") (name "Net-(Q28-S)") (class "Default")
      (node (ref "Q26") (pin "2") (pinfunction "D_2") (pintype "passive"))
      (node (ref "Q26") (pin "4") (pinfunction "D_4") (pintype "passive"))
      (node (ref "Q26") (pin "P$1") (pinfunction "D_P$1") (pintype "passive"))
      (node (ref "Q26") (pin "P$10") (pinfunction "D_P$10") (pintype "passive"))
      (node (ref "Q26") (pin "P$11") (pinfunction "D_P$11") (pintype "passive"))
      (node (ref "Q26") (pin "P$12") (pinfunction "D_P$12") (pintype "passive"))
      (node (ref "Q26") (pin "P$13") (pinfunction "D_P$13") (pintype "passive"))
      (node (ref "Q26") (pin "P$14") (pinfunction "D_P$14") (pintype "passive"))
      (node (ref "Q26") (pin "P$15") (pinfunction "D_P$15") (pintype "passive"))
      (node (ref "Q26") (pin "P$16") (pinfunction "D_P$16") (pintype "passive"))
      (node (ref "Q26") (pin "P$17") (pinfunction "D_P$17") (pintype "passive"))
      (node (ref "Q26") (pin "P$18") (pinfunction "D_P$18") (pintype "passive"))
      (node (ref "Q26") (pin "P$19") (pinfunction "D_P$19") (pintype "passive"))
      (node (ref "Q26") (pin "P$2") (pinfunction "D_P$2") (pintype "passive"))
      (node (ref "Q26") (pin "P$20") (pinfunction "D_P$20") (pintype "passive"))
      (node (ref "Q26") (pin "P$21") (pinfunction "D_P$21") (pintype "passive"))
      (node (ref "Q26") (pin "P$22") (pinfunction "D_P$22") (pintype "passive"))
      (node (ref "Q26") (pin "P$23") (pinfunction "D_P$23") (pintype "passive"))
      (node (ref "Q26") (pin "P$24") (pinfunction "D_P$24") (pintype "passive"))
      (node (ref "Q26") (pin "P$25") (pinfunction "D_P$25") (pintype "passive"))
      (node (ref "Q26") (pin "P$26") (pinfunction "D_P$26") (pintype "passive"))
      (node (ref "Q26") (pin "P$27") (pinfunction "D_P$27") (pintype "passive"))
      (node (ref "Q26") (pin "P$28") (pinfunction "D_P$28") (pintype "passive"))
      (node (ref "Q26") (pin "P$29") (pinfunction "D_P$29") (pintype "passive"))
      (node (ref "Q26") (pin "P$3") (pinfunction "D_P$3") (pintype "passive"))
      (node (ref "Q26") (pin "P$30") (pinfunction "D_P$30") (pintype "passive"))
      (node (ref "Q26") (pin "P$31") (pinfunction "D_P$31") (pintype "passive"))
      (node (ref "Q26") (pin "P$32") (pinfunction "D_P$32") (pintype "passive"))
      (node (ref "Q26") (pin "P$33") (pinfunction "D_P$33") (pintype "passive"))
      (node (ref "Q26") (pin "P$34") (pinfunction "D_P$34") (pintype "passive"))
      (node (ref "Q26") (pin "P$35") (pinfunction "D_P$35") (pintype "passive"))
      (node (ref "Q26") (pin "P$36") (pinfunction "D_P$36") (pintype "passive"))
      (node (ref "Q26") (pin "P$37") (pinfunction "D_P$37") (pintype "passive"))
      (node (ref "Q26") (pin "P$38") (pinfunction "D_P$38") (pintype "passive"))
      (node (ref "Q26") (pin "P$39") (pinfunction "D_P$39") (pintype "passive"))
      (node (ref "Q26") (pin "P$4") (pinfunction "D_P$4") (pintype "passive"))
      (node (ref "Q26") (pin "P$40") (pinfunction "D_P$40") (pintype "passive"))
      (node (ref "Q26") (pin "P$41") (pinfunction "D_P$41") (pintype "passive"))
      (node (ref "Q26") (pin "P$42") (pinfunction "D_P$42") (pintype "passive"))
      (node (ref "Q26") (pin "P$43") (pinfunction "D_P$43") (pintype "passive"))
      (node (ref "Q26") (pin "P$44") (pinfunction "D_P$44") (pintype "passive"))
      (node (ref "Q26") (pin "P$45") (pinfunction "D_P$45") (pintype "passive"))
      (node (ref "Q26") (pin "P$46") (pinfunction "D_P$46") (pintype "passive"))
      (node (ref "Q26") (pin "P$47") (pinfunction "D_P$47") (pintype "passive"))
      (node (ref "Q26") (pin "P$48") (pinfunction "D_P$48") (pintype "passive"))
      (node (ref "Q26") (pin "P$49") (pinfunction "D_P$49") (pintype "passive"))
      (node (ref "Q26") (pin "P$5") (pinfunction "D_P$5") (pintype "passive"))
      (node (ref "Q26") (pin "P$50") (pinfunction "D_P$50") (pintype "passive"))
      (node (ref "Q26") (pin "P$51") (pinfunction "D_P$51") (pintype "passive"))
      (node (ref "Q26") (pin "P$52") (pinfunction "D_P$52") (pintype "passive"))
      (node (ref "Q26") (pin "P$53") (pinfunction "D_P$53") (pintype "passive"))
      (node (ref "Q26") (pin "P$54") (pinfunction "D_P$54") (pintype "passive"))
      (node (ref "Q26") (pin "P$55") (pinfunction "D_P$55") (pintype "passive"))
      (node (ref "Q26") (pin "P$56") (pinfunction "D_P$56") (pintype "passive"))
      (node (ref "Q26") (pin "P$57") (pinfunction "D_P$57") (pintype "passive"))
      (node (ref "Q26") (pin "P$58") (pinfunction "D_P$58") (pintype "passive"))
      (node (ref "Q26") (pin "P$59") (pinfunction "D_P$59") (pintype "passive"))
      (node (ref "Q26") (pin "P$6") (pinfunction "D_P$6") (pintype "passive"))
      (node (ref "Q26") (pin "P$60") (pinfunction "D_P$60") (pintype "passive"))
      (node (ref "Q26") (pin "P$61") (pinfunction "D_P$61") (pintype "passive"))
      (node (ref "Q26") (pin "P$62") (pinfunction "D_P$62") (pintype "passive"))
      (node (ref "Q26") (pin "P$63") (pinfunction "D_P$63") (pintype "passive"))
      (node (ref "Q26") (pin "P$7") (pinfunction "D_P$7") (pintype "passive"))
      (node (ref "Q26") (pin "P$8") (pinfunction "D_P$8") (pintype "passive"))
      (node (ref "Q26") (pin "P$9") (pinfunction "D_P$9") (pintype "passive"))
      (node (ref "Q28") (pin "3") (pinfunction "S_3") (pintype "passive"))
    )
    (net (code "42") (name "Net-(SJ1-1)") (class "Default")
      (node (ref "R45") (pin "2") (pinfunction "2_2") (pintype "passive"))
      (node (ref "SJ1") (pin "P$1") (pinfunction "1_P$1") (pintype "passive"))
    )
    (net (code "43") (name "Net-(SJ2-1)") (class "Default")
      (node (ref "R46") (pin "2") (pinfunction "2_2") (pintype "passive"))
      (node (ref "SJ2") (pin "P$1") (pinfunction "1_P$1") (pintype "passive"))
    )
    (net (code "44") (name "Net-(U$1A-D)") (class "Default")
      (node (ref "U$1") (pin "2") (pinfunction "D_2") (pintype "passive"))
      (node (ref "U$2") (pin "5") (pinfunction "E_5") (pintype "passive"))
    )
    (net (code "45") (name "Net-(U$1A-S)") (class "Default")
      (node (ref "U$1") (pin "3") (pinfunction "S_3") (pintype "passive"))
      (node (ref "VR4") (pin "3") (pinfunction "E_3") (pintype "passive"))
    )
    (net (code "46") (name "Net-(U$1B-D)") (class "Default")
      (node (ref "U$1") (pin "5") (pinfunction "D_5") (pintype "passive"))
      (node (ref "U$2") (pin "2") (pinfunction "E_2") (pintype "passive"))
    )
    (net (code "47") (name "Net-(U$1B-S)") (class "Default")
      (node (ref "U$1") (pin "6") (pinfunction "S_6") (pintype "passive"))
      (node (ref "VR4") (pin "1") (pinfunction "A_1") (pintype "passive"))
    )
    (net (code "48") (name "Net-(U$2A-B)") (class "Default")
      (node (ref "CR1") (pin "CATHODE") (pinfunction "CATHODE_CATHODE") (pintype "passive"))
      (node (ref "D1") (pin "C") (pinfunction "C_C") (pintype "passive"))
      (node (ref "U$2") (pin "1") (pinfunction "B_1") (pintype "passive"))
      (node (ref "U$2") (pin "3") (pinfunction "B_3") (pintype "passive"))
    )
    (net (code "49") (name "Net-(U$3A-D)") (class "Default")
      (node (ref "U$3") (pin "2") (pinfunction "D_2") (pintype "passive"))
      (node (ref "U$6") (pin "5") (pinfunction "E_5") (pintype "passive"))
    )
    (net (code "50") (name "Net-(U$3A-S)") (class "Default")
      (node (ref "D11") (pin "A") (pinfunction "A_A") (pintype "passive"))
      (node (ref "R43") (pin "1") (pinfunction "1_1") (pintype "passive"))
      (node (ref "U$3") (pin "3") (pinfunction "S_3") (pintype "passive"))
      (node (ref "U$3") (pin "6") (pinfunction "S_6") (pintype "passive"))
    )
    (net (code "51") (name "Net-(U$3B-D)") (class "Default")
      (node (ref "U$3") (pin "5") (pinfunction "D_5") (pintype "passive"))
      (node (ref "U$6") (pin "2") (pinfunction "E_2") (pintype "passive"))
    )
    (net (code "52") (name "Net-(U$4-B1)") (class "Default")
      (node (ref "R25") (pin "1") (pinfunction "1_1") (pintype "passive"))
      (node (ref "U$4") (pin "1") (pinfunction "B1_1") (pintype "passive"))
      (node (ref "VR3") (pin "1") (pinfunction "A_1") (pintype "passive"))
      (node (ref "VR3") (pin "2") (pinfunction "S_2") (pintype "passive"))
    )
    (net (code "53") (name "Net-(U$4-B2)") (class "Default")
      (node (ref "R26") (pin "2") (pinfunction "2_2") (pintype "passive"))
      (node (ref "R27") (pin "1") (pinfunction "1_1") (pintype "passive"))
      (node (ref "U$4") (pin "3") (pinfunction "B2_3") (pintype "passive"))
    )
    (net (code "54") (name "Net-(U$5A-S)") (class "Default")
      (node (ref "R8") (pin "1") (pinfunction "1_1") (pintype "passive"))
      (node (ref "U$5") (pin "3") (pinfunction "S_3") (pintype "passive"))
    )
    (net (code "55") (name "Net-(U$5B-S)") (class "Default")
      (node (ref "R7") (pin "2") (pinfunction "2_2") (pintype "passive"))
      (node (ref "U$5") (pin "6") (pinfunction "S_6") (pintype "passive"))
    )
    (net (code "56") (name "Net-(U$6A-B)") (class "Default")
      (node (ref "CR3") (pin "CATHODE") (pinfunction "CATHODE_CATHODE") (pintype "passive"))
      (node (ref "D11") (pin "C") (pinfunction "C_C") (pintype "passive"))
      (node (ref "U$6") (pin "1") (pinfunction "B_1") (pintype "passive"))
      (node (ref "U$6") (pin "3") (pinfunction "B_3") (pintype "passive"))
    )
    (net (code "57") (name "Net-(U$6A-C)") (class "Default")
      (node (ref "C1") (pin "2") (pinfunction "2_2") (pintype "passive"))
      (node (ref "R37") (pin "2") (pinfunction "2_2") (pintype "passive"))
      (node (ref "U$6") (pin "6") (pinfunction "C_6") (pintype "passive"))
    )
    (net (code "58") (name "Net-(U$7A-C)") (class "Default")
      (node (ref "U$7") (pin "6") (pinfunction "C_6") (pintype "passive"))
      (node (ref "U$8") (pin "5") (pinfunction "E_5") (pintype "passive"))
    )
    (net (code "59") (name "Net-(U$7A-E)") (class "Default")
      (node (ref "R19") (pin "2") (pinfunction "2_2") (pintype "passive"))
      (node (ref "U$7") (pin "5") (pinfunction "E_5") (pintype "passive"))
    )
    (net (code "60") (name "Net-(U$7B-C)") (class "Default")
      (node (ref "U$7") (pin "4") (pinfunction "C_4") (pintype "passive"))
      (node (ref "U$8") (pin "2") (pinfunction "E_2") (pintype "passive"))
    )
    (net (code "61") (name "Net-(U$7B-E)") (class "Default")
      (node (ref "R18") (pin "1") (pinfunction "1_1") (pintype "passive"))
      (node (ref "U$7") (pin "2") (pinfunction "E_2") (pintype "passive"))
    )
    (net (code "62") (name "Net-(U$8A-B)") (class "Default")
      (node (ref "CR6") (pin "CATHODE") (pinfunction "CATHODE_CATHODE") (pintype "passive"))
      (node (ref "D8") (pin "C") (pinfunction "C_C") (pintype "passive"))
      (node (ref "U$8") (pin "1") (pinfunction "B_1") (pintype "passive"))
    )
    (net (code "63") (name "Net-(U$8B-B)") (class "Default")
      (node (ref "CR5") (pin "CATHODE") (pinfunction "CATHODE_CATHODE") (pintype "passive"))
      (node (ref "D7") (pin "C") (pinfunction "C_C") (pintype "passive"))
      (node (ref "U$8") (pin "3") (pinfunction "B_3") (pintype "passive"))
    )
    (net (code "64") (name "Net-(U$9A-B)") (class "Default")
      (node (ref "CR4") (pin "ANODE") (pinfunction "ANODE_ANODE") (pintype "passive"))
      (node (ref "D12") (pin "A") (pinfunction "A_A") (pintype "passive"))
      (node (ref "U$9") (pin "1") (pinfunction "B_1") (pintype "passive"))
      (node (ref "U$9") (pin "3") (pinfunction "B_3") (pintype "passive"))
    )
    (net (code "65") (name "Net-(U$9B-C)") (class "Default")
      (node (ref "C11") (pin "1") (pinfunction "1_1") (pintype "passive"))
      (node (ref "R39") (pin "1") (pinfunction "1_1") (pintype "passive"))
      (node (ref "U$9") (pin "4") (pinfunction "C_4") (pintype "passive"))
    )
    (net (code "66") (name "Net-(U$10A-B)") (class "Default")
      (node (ref "CR2") (pin "ANODE") (pinfunction "ANODE_ANODE") (pintype "passive"))
      (node (ref "D2") (pin "A") (pinfunction "A_A") (pintype "passive"))
      (node (ref "U$10") (pin "1") (pinfunction "B_1") (pintype "passive"))
      (node (ref "U$10") (pin "3") (pinfunction "B_3") (pintype "passive"))
    )
    (net (code "67") (name "Net-(U$10A-C)") (class "Default")
      (node (ref "C5") (pin "2") (pinfunction "2_2") (pintype "passive"))
      (node (ref "R12") (pin "1") (pinfunction "1_1") (pintype "passive"))
      (node (ref "U$10") (pin "6") (pinfunction "C_6") (pintype "passive"))
      (node (ref "U$7") (pin "1") (pinfunction "B_1") (pintype "passive"))
    )
    (net (code "68") (name "Net-(U$10A-E)") (class "Default")
      (node (ref "U$10") (pin "5") (pinfunction "E_5") (pintype "passive"))
      (node (ref "U$5") (pin "2") (pinfunction "D_2") (pintype "passive"))
    )
    (net (code "69") (name "Net-(U$10B-C)") (class "Default")
      (node (ref "C4") (pin "2") (pinfunction "2_2") (pintype "passive"))
      (node (ref "R11") (pin "1") (pinfunction "1_1") (pintype "passive"))
      (node (ref "U$10") (pin "4") (pinfunction "C_4") (pintype "passive"))
      (node (ref "U$7") (pin "3") (pinfunction "B_3") (pintype "passive"))
    )
    (net (code "70") (name "Net-(U$10B-E)") (class "Default")
      (node (ref "U$10") (pin "2") (pinfunction "E_2") (pintype "passive"))
      (node (ref "U$5") (pin "5") (pinfunction "D_5") (pintype "passive"))
    )
    (net (code "71") (name "Net-(U$11A-B)") (class "Default")
      (node (ref "C3") (pin "2") (pinfunction "2_2") (pintype "passive"))
      (node (ref "R10") (pin "2") (pinfunction "2_2") (pintype "passive"))
      (node (ref "U$11") (pin "1") (pinfunction "B_1") (pintype "passive"))
      (node (ref "U$2") (pin "4") (pinfunction "C_4") (pintype "passive"))
    )
    (net (code "72") (name "Net-(U$11A-C)") (class "Default")
      (node (ref "U$11") (pin "6") (pinfunction "C_6") (pintype "passive"))
      (node (ref "U$12") (pin "5") (pinfunction "E_5") (pintype "passive"))
    )
    (net (code "73") (name "Net-(U$11A-E)") (class "Default")
      (node (ref "R17") (pin "2") (pinfunction "2_2") (pintype "passive"))
      (node (ref "U$11") (pin "5") (pinfunction "E_5") (pintype "passive"))
    )
    (net (code "74") (name "Net-(U$11B-B)") (class "Default")
      (node (ref "C2") (pin "2") (pinfunction "2_2") (pintype "passive"))
      (node (ref "R9") (pin "2") (pinfunction "2_2") (pintype "passive"))
      (node (ref "U$11") (pin "3") (pinfunction "B_3") (pintype "passive"))
      (node (ref "U$2") (pin "6") (pinfunction "C_6") (pintype "passive"))
    )
    (net (code "75") (name "Net-(U$11B-C)") (class "Default")
      (node (ref "U$11") (pin "4") (pinfunction "C_4") (pintype "passive"))
      (node (ref "U$12") (pin "2") (pinfunction "E_2") (pintype "passive"))
    )
    (net (code "76") (name "Net-(U$11B-E)") (class "Default")
      (node (ref "R16") (pin "1") (pinfunction "1_1") (pintype "passive"))
      (node (ref "U$11") (pin "2") (pinfunction "E_2") (pintype "passive"))
    )
    (net (code "77") (name "Net-(U$12A-B)") (class "Default")
      (node (ref "CR6") (pin "ANODE") (pinfunction "ANODE_ANODE") (pintype "passive"))
      (node (ref "D6") (pin "A") (pinfunction "A_A") (pintype "passive"))
      (node (ref "U$12") (pin "1") (pinfunction "B_1") (pintype "passive"))
    )
    (net (code "78") (name "Net-(U$12B-B)") (class "Default")
      (node (ref "CR5") (pin "ANODE") (pinfunction "ANODE_ANODE") (pintype "passive"))
      (node (ref "D5") (pin "A") (pinfunction "A_A") (pintype "passive"))
      (node (ref "U$12") (pin "3") (pinfunction "B_3") (pintype "passive"))
    )
    (net (code "79") (name "Net-(U$13A-B)") (class "Default")
      (node (ref "C12") (pin "1") (pinfunction "1_1") (pintype "passive"))
      (node (ref "U$13") (pin "1") (pinfunction "B_1") (pintype "passive"))
      (node (ref "U$13") (pin "3") (pinfunction "B_3") (pintype "passive"))
      (node (ref "U$13") (pin "4") (pinfunction "C_4") (pintype "passive"))
      (node (ref "U$9") (pin "6") (pinfunction "C_6") (pintype "passive"))
    )
    (net (code "80") (name "Net-(U$13A-E)") (class "Default")
      (node (ref "R44") (pin "1") (pinfunction "1_1") (pintype "passive"))
      (node (ref "U$13") (pin "5") (pinfunction "E_5") (pintype "passive"))
    )
    (net (code "81") (name "Net-(U$13B-E)") (class "Default")
      (node (ref "R40") (pin "1") (pinfunction "1_1") (pintype "passive"))
      (node (ref "U$13") (pin "2") (pinfunction "E_2") (pintype "passive"))
    )
    (net (code "82") (name "Net-(U$14A-B)") (class "Default")
      (node (ref "C10") (pin "2") (pinfunction "2_2") (pintype "passive"))
      (node (ref "U$14") (pin "1") (pinfunction "B_1") (pintype "passive"))
      (node (ref "U$14") (pin "3") (pinfunction "B_3") (pintype "passive"))
      (node (ref "U$14") (pin "4") (pinfunction "C_4") (pintype "passive"))
      (node (ref "U$6") (pin "4") (pinfunction "C_4") (pintype "passive"))
    )
    (net (code "83") (name "Net-(U$14A-E)") (class "Default")
      (node (ref "R42") (pin "2") (pinfunction "2_2") (pintype "passive"))
      (node (ref "U$14") (pin "5") (pinfunction "E_5") (pintype "passive"))
    )
    (net (code "84") (name "Net-(U$14B-E)") (class "Default")
      (node (ref "R38") (pin "2") (pinfunction "2_2") (pintype "passive"))
      (node (ref "U$14") (pin "2") (pinfunction "E_2") (pintype "passive"))
    )
    (net (code "85") (name "Net-(U$15A-D)") (class "Default")
      (node (ref "U$15") (pin "2") (pinfunction "D_2") (pintype "passive"))
      (node (ref "U$9") (pin "5") (pinfunction "E_5") (pintype "passive"))
    )
    (net (code "86") (name "Net-(U$15A-G)") (class "Default")
      (node (ref "C10") (pin "1") (pinfunction "1_1") (pintype "passive"))
      (node (ref "C12") (pin "2") (pinfunction "2_2") (pintype "passive"))
      (node (ref "R41") (pin "1") (pinfunction "1_1") (pintype "passive"))
      (node (ref "U$15") (pin "1") (pinfunction "G_1") (pintype "passive"))
      (node (ref "U$3") (pin "4") (pinfunction "G_4") (pintype "passive"))
    )
    (net (code "87") (name "Net-(U$15A-S)") (class "Default")
      (node (ref "D12") (pin "C") (pinfunction "C_C") (pintype "passive"))
      (node (ref "R43") (pin "2") (pinfunction "2_2") (pintype "passive"))
      (node (ref "U$15") (pin "3") (pinfunction "S_3") (pintype "passive"))
      (node (ref "U$15") (pin "6") (pinfunction "S_6") (pintype "passive"))
    )
    (net (code "88") (name "Net-(U$15B-D)") (class "Default")
      (node (ref "U$15") (pin "5") (pinfunction "D_5") (pintype "passive"))
      (node (ref "U$9") (pin "2") (pinfunction "E_2") (pintype "passive"))
    )
    (net (code "89") (name "Net-(U$15B-G)") (class "Default")
      (node (ref "C1") (pin "1") (pinfunction "1_1") (pintype "passive"))
      (node (ref "C11") (pin "2") (pinfunction "2_2") (pintype "passive"))
      (node (ref "R3") (pin "2") (pinfunction "2_2") (pintype "passive"))
      (node (ref "R4") (pin "1") (pinfunction "1_1") (pintype "passive"))
      (node (ref "U$15") (pin "4") (pinfunction "G_4") (pintype "passive"))
      (node (ref "U$3") (pin "1") (pinfunction "G_1") (pintype "passive"))
    )
    (net (code "90") (name "Net-(U$16-B1)") (class "Default")
      (node (ref "R1") (pin "1") (pinfunction "1_1") (pintype "passive"))
      (node (ref "U$16") (pin "1") (pinfunction "B1_1") (pintype "passive"))
      (node (ref "VR2") (pin "1") (pinfunction "A_1") (pintype "passive"))
      (node (ref "VR2") (pin "2") (pinfunction "S_2") (pintype "passive"))
    )
    (net (code "91") (name "Net-(U$16-B2)") (class "Default")
      (node (ref "R2") (pin "2") (pinfunction "2_2") (pintype "passive"))
      (node (ref "R5") (pin "1") (pinfunction "1_1") (pintype "passive"))
      (node (ref "U$16") (pin "3") (pinfunction "B2_3") (pintype "passive"))
    )
    (net (code "92") (name "Net-(VR1-A)") (class "Default")
      (node (ref "D1") (pin "A") (pinfunction "A_A") (pintype "passive"))
      (node (ref "VR1") (pin "1") (pinfunction "A_1") (pintype "passive"))
      (node (ref "VR1") (pin "2") (pinfunction "S_2") (pintype "passive"))
      (node (ref "VR4") (pin "2") (pinfunction "S_2") (pintype "passive"))
    )
    (net (code "93") (name "Net-(VR1-E)") (class "Default")
      (node (ref "D2") (pin "C") (pinfunction "C_C") (pintype "passive"))
      (node (ref "R7") (pin "1") (pinfunction "1_1") (pintype "passive"))
      (node (ref "R8") (pin "2") (pinfunction "2_2") (pintype "passive"))
      (node (ref "VR1") (pin "3") (pinfunction "E_3") (pintype "passive"))
    )
    (net (code "94") (name "Net-(VR2-E)") (class "Default")
      (node (ref "R5") (pin "2") (pinfunction "2_2") (pintype "passive"))
      (node (ref "VR2") (pin "3") (pinfunction "E_3") (pintype "passive"))
    )
    (net (code "95") (name "Net-(VR3-E)") (class "Default")
      (node (ref "R27") (pin "2") (pinfunction "2_2") (pintype "passive"))
      (node (ref "VR3") (pin "3") (pinfunction "E_3") (pintype "passive"))
    )
    (net (code "96") (name "unconnected-(U$4-E-Pad2)") (class "Default")
      (node (ref "U$4") (pin "2") (pinfunction "E_2") (pintype "passive"))
    )
    (net (code "97") (name "unconnected-(U$16-E-Pad2)") (class "Default")
      (node (ref "U$16") (pin "2") (pinfunction "E_2") (pintype "passive"))
    )
  )
)
